# EEZ_CF-DIC_r5B5.net
KiCad netlist of a schematic drawn in EAGLE
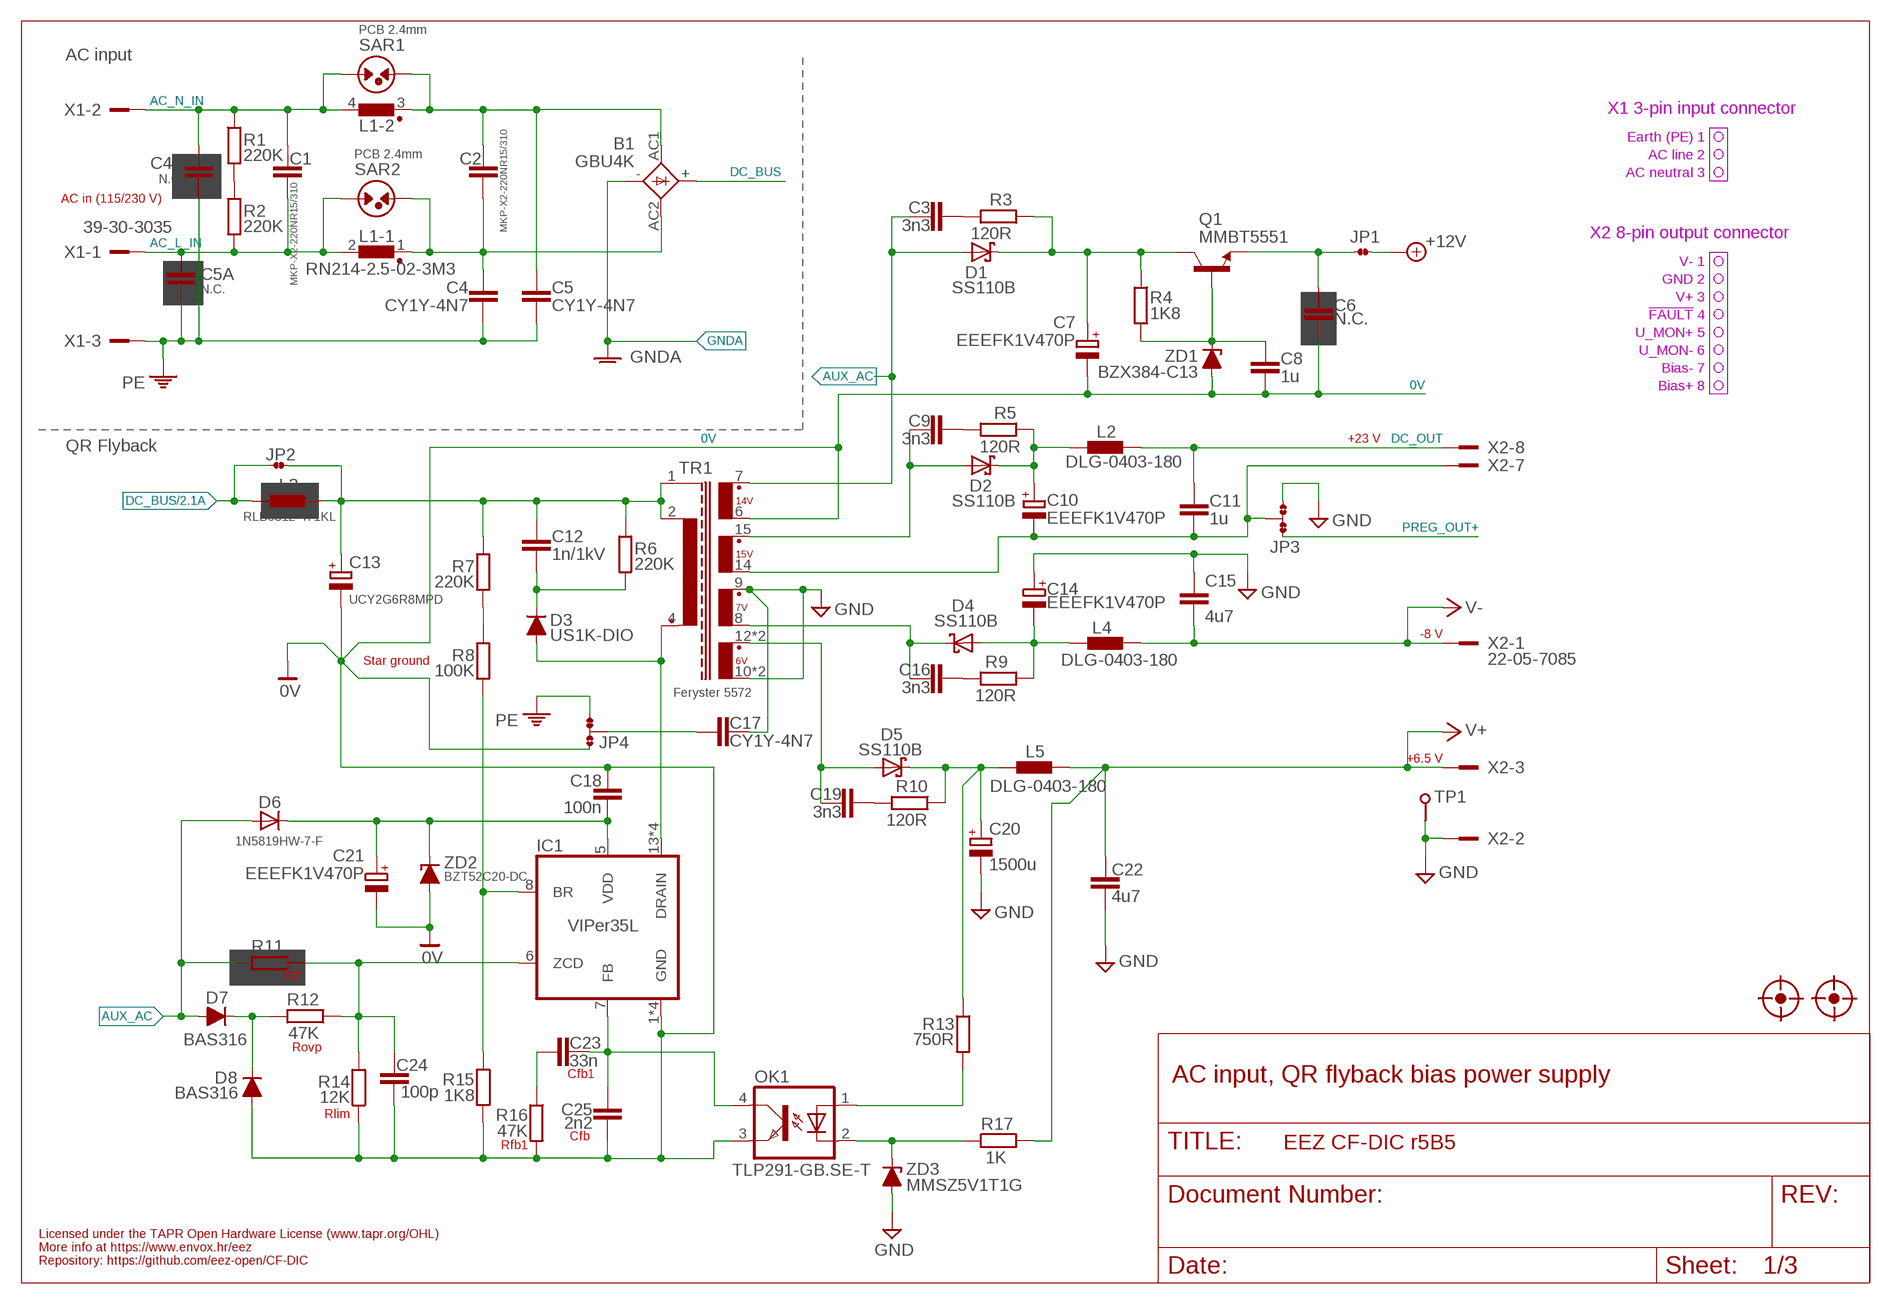
[diagram p0: schematic, sheet 1]
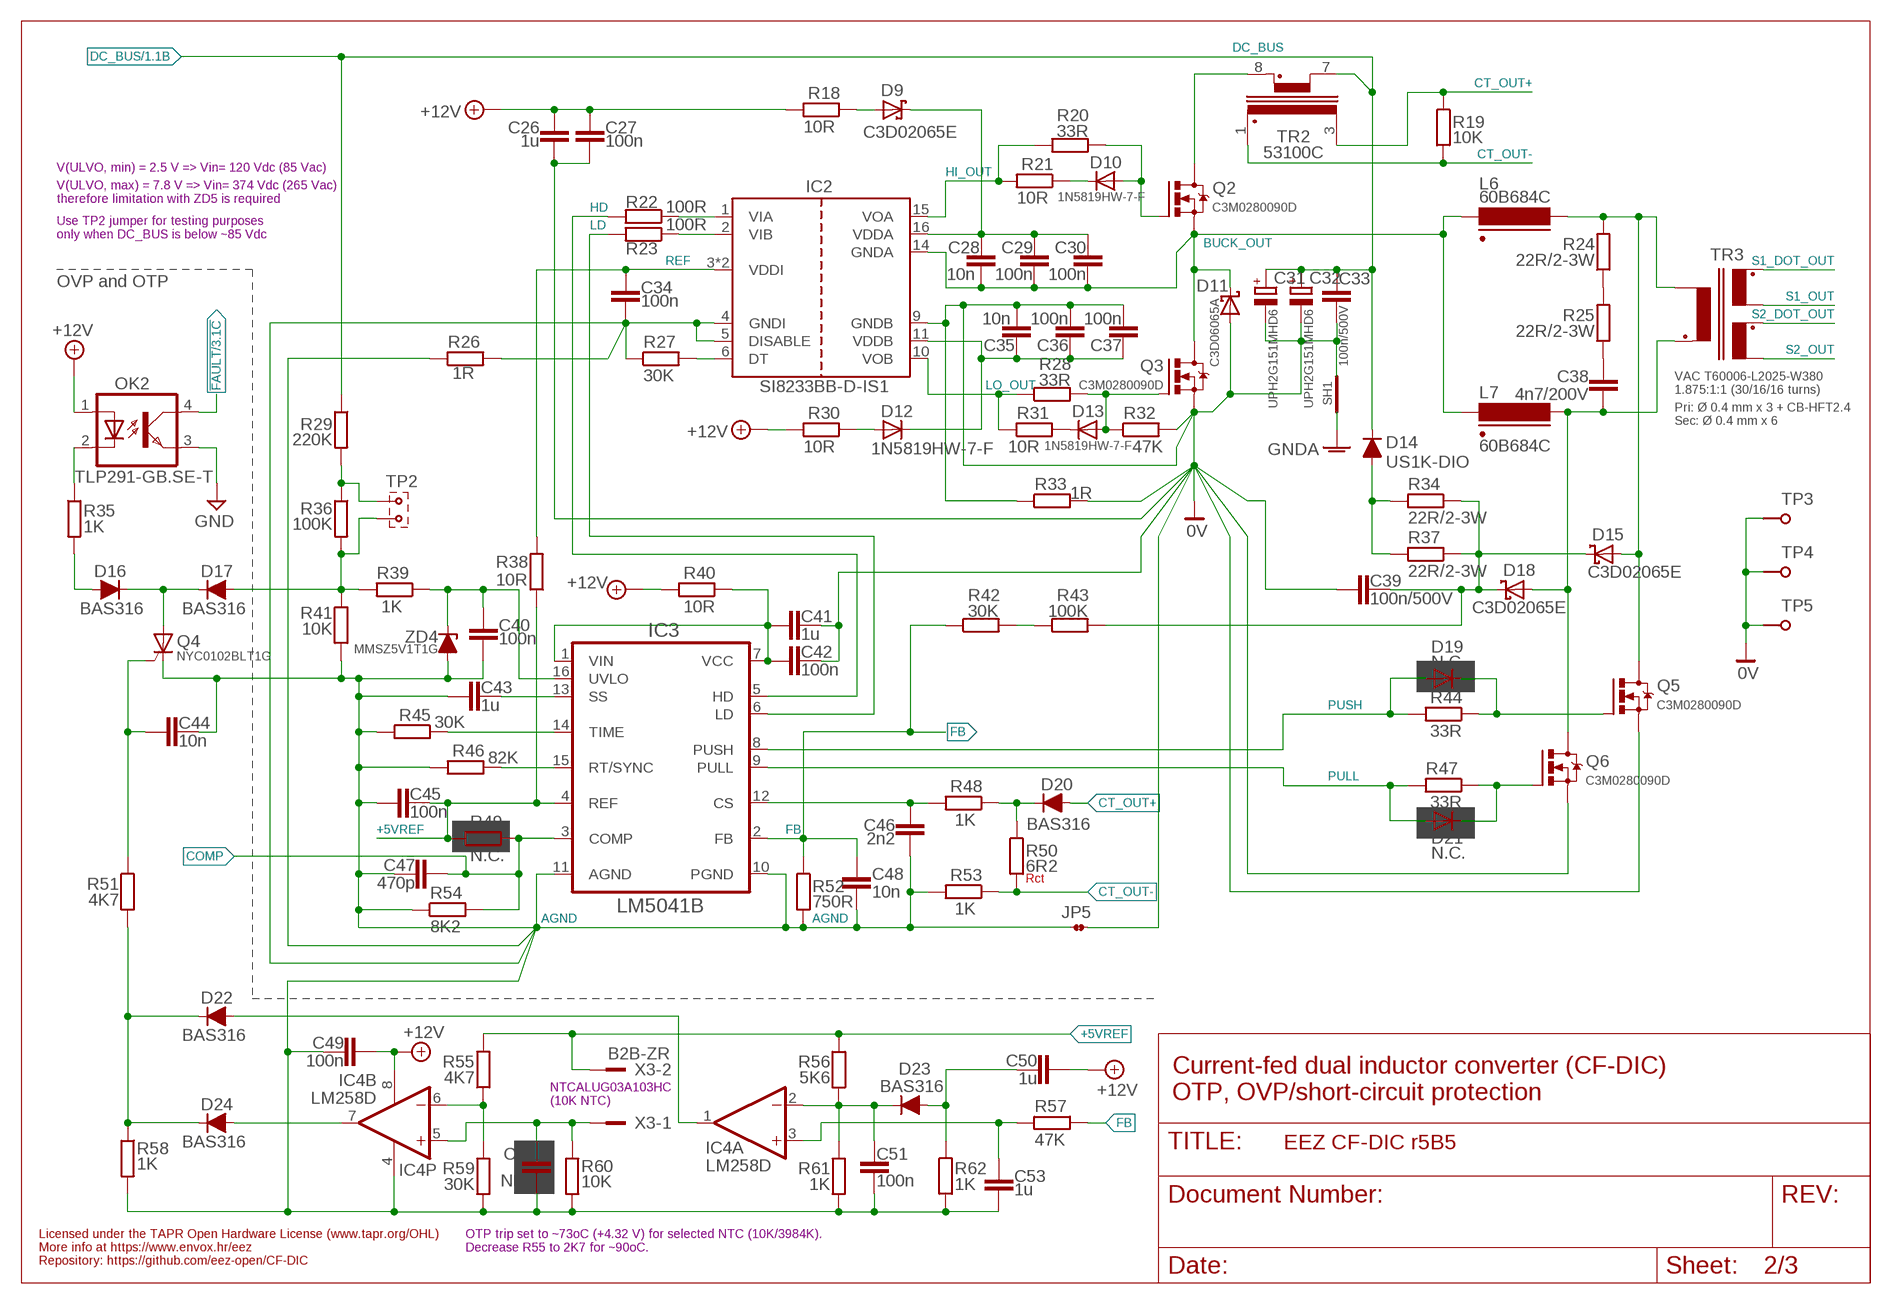
[diagram p1: schematic, sheet 2]
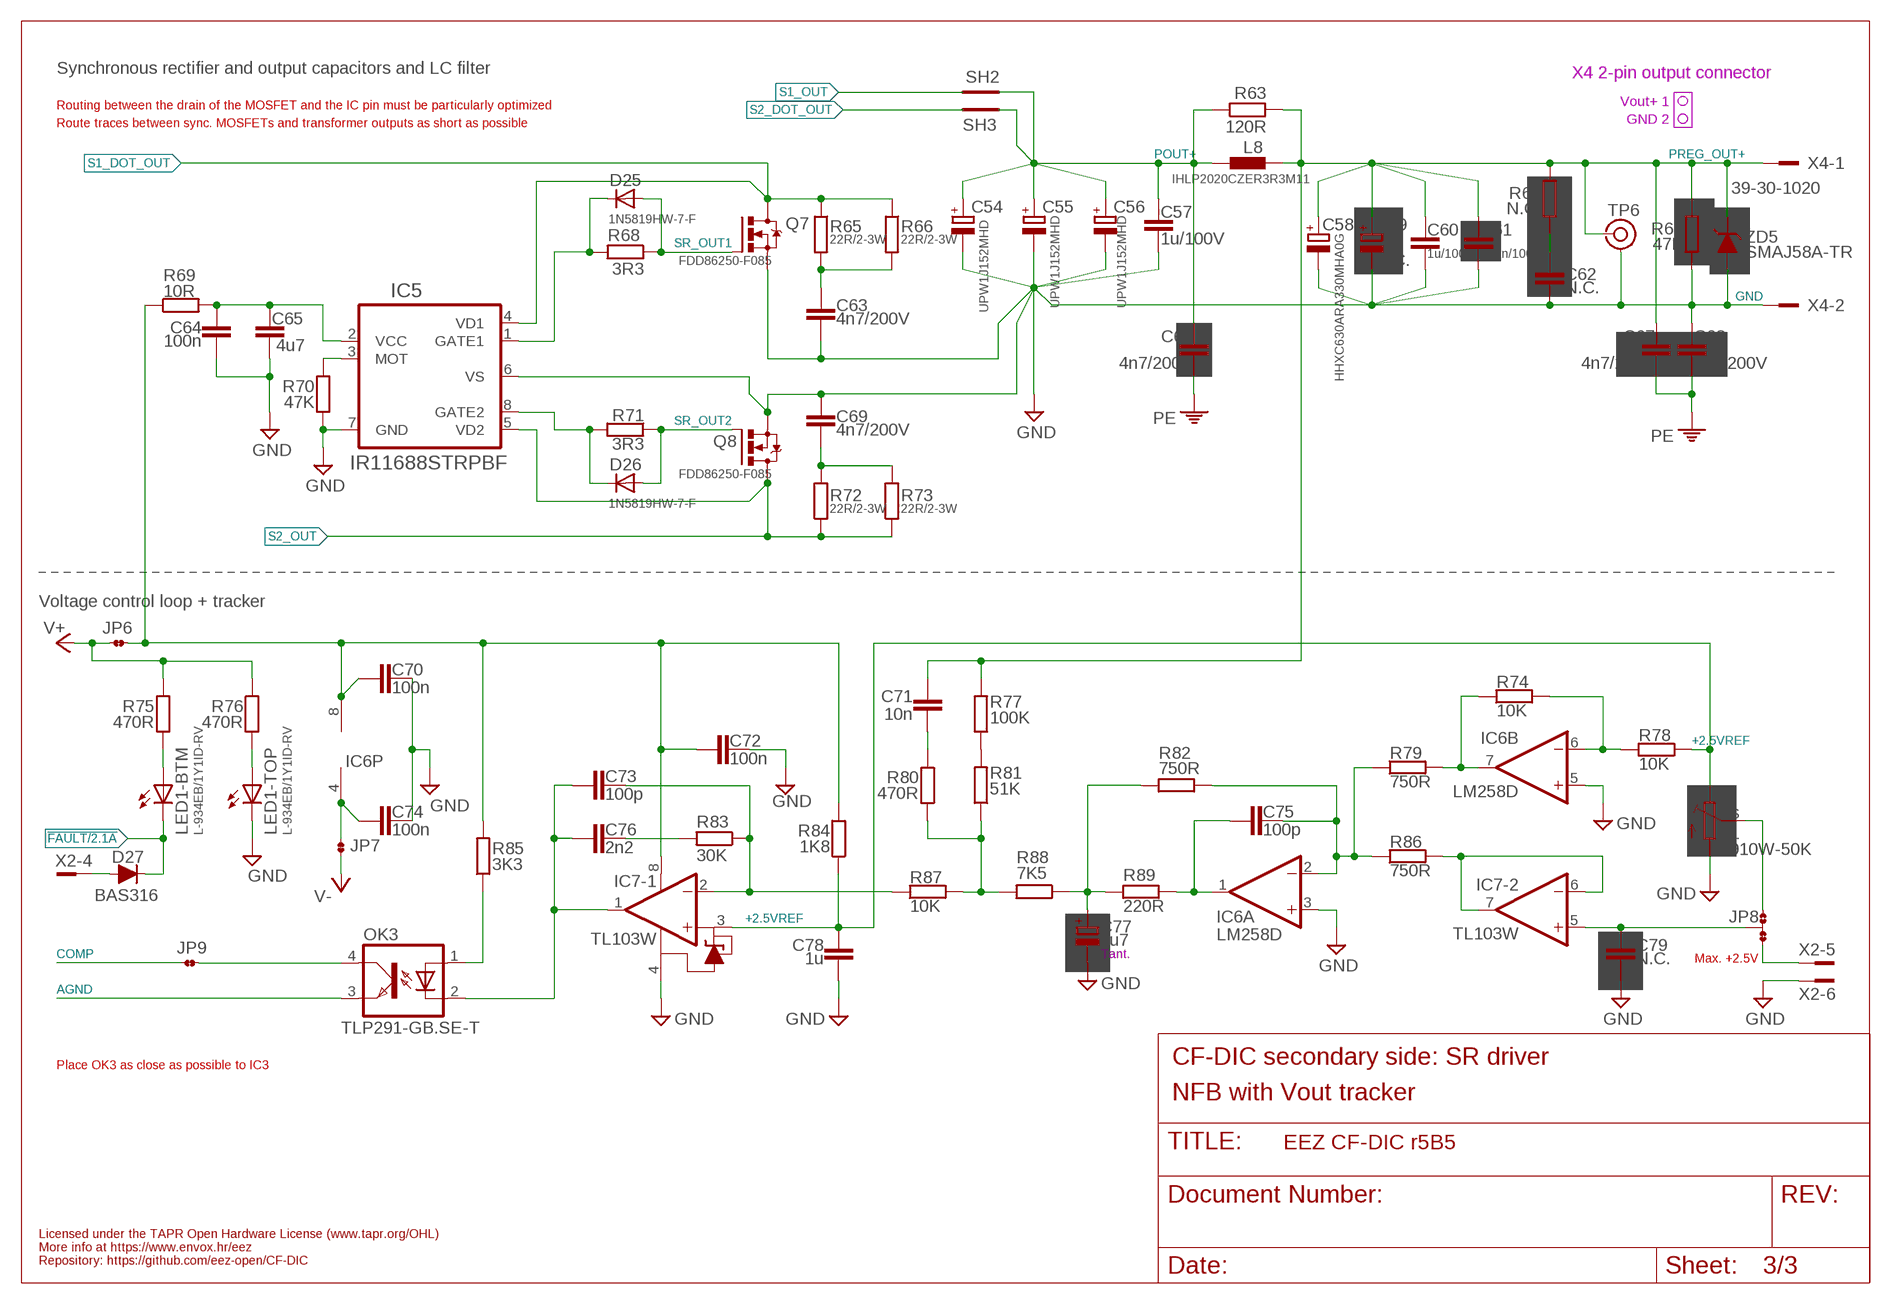
[diagram p2: schematic, sheet 3]

(export (version "E")
  (design (tool "Eeschema 10.0.6"))
  (components
    (comp (ref "B1")
      (value "GBU4K")
      (footprint "eagle-import:GBU4K_CRE")
      (libsource (lib "eagle-import") (part "BRIDGE-CREEPAGE"))
    )
    (comp (ref "C1")
      (value "MKP-X2-220NR15/310")
      (footprint "eagle-import:C150-072X183")
      (libsource (lib "eagle-import") (part "C-EU150-072X183"))
    )
    (comp (ref "C2")
      (value "MKP-X2-220NR15/310")
      (footprint "eagle-import:C150-072X183")
      (libsource (lib "eagle-import") (part "C-EU150-072X183"))
    )
    (comp (ref "C3")
      (value "3n3")
      (footprint "eagle-import:C0805")
      (libsource (lib "eagle-import") (part "C-EUC0805"))
    )
    (comp (ref "C4")
      (value "CY1Y-4N7")
      (footprint "eagle-import:CY075-032X103")
      (libsource (lib "eagle-import") (part "C-EUCY"))
    )
    (comp (ref "C4A")
      (value "N.C.")
      (footprint "eagle-import:CY075-032X103-ROTATED")
      (libsource (lib "eagle-import") (part "C-EUCY-ROTATED"))
    )
    (comp (ref "C5")
      (value "CY1Y-4N7")
      (footprint "eagle-import:CY075-032X103")
      (libsource (lib "eagle-import") (part "C-EUCY"))
    )
    (comp (ref "C5A")
      (value "N.C.")
      (footprint "eagle-import:CY075-032X103")
      (libsource (lib "eagle-import") (part "C-EUCY"))
    )
    (comp (ref "C6")
      (value "N.C.")
      (footprint "eagle-import:C0603")
      (libsource (lib "eagle-import") (part "C-EUC0603"))
    )
    (comp (ref "C7")
      (value "EEEFK1V470P")
      (footprint "eagle-import:CAPAE660X610N")
      (libsource (lib "eagle-import") (part "ECAPPANASONIC_H"))
    )
    (comp (ref "C8")
      (value "1u")
      (footprint "eagle-import:C0805")
      (libsource (lib "eagle-import") (part "C-EUC0805"))
    )
    (comp (ref "C9")
      (value "3n3")
      (footprint "eagle-import:C0805")
      (libsource (lib "eagle-import") (part "C-EUC0805"))
    )
    (comp (ref "C10")
      (value "EEEFK1V470P")
      (footprint "eagle-import:CAPAE660X610N")
      (libsource (lib "eagle-import") (part "ECAPPANASONIC_H"))
    )
    (comp (ref "C11")
      (value "1u")
      (footprint "eagle-import:C0805")
      (libsource (lib "eagle-import") (part "C-EUC0805"))
    )
    (comp (ref "C12")
      (value "1n/1kV")
      (footprint "eagle-import:C1210")
      (libsource (lib "eagle-import") (part "C-EUC1210"))
    )
    (comp (ref "C13")
      (value "UCY2G6R8MPD")
      (footprint "eagle-import:ECAP5_10.5")
      (libsource (lib "eagle-import") (part "ECAP5G_10.5MM"))
    )
    (comp (ref "C14")
      (value "EEEFK1V470P")
      (footprint "eagle-import:CAPAE660X610N")
      (libsource (lib "eagle-import") (part "ECAPPANASONIC_H"))
    )
    (comp (ref "C15")
      (value "4u7")
      (footprint "eagle-import:C1206")
      (libsource (lib "eagle-import") (part "C-EUC1206"))
    )
    (comp (ref "C16")
      (value "3n3")
      (footprint "eagle-import:C0805")
      (libsource (lib "eagle-import") (part "C-EUC0805"))
    )
    (comp (ref "C17")
      (value "CY1Y-4N7")
      (footprint "eagle-import:CY075-032X103")
      (libsource (lib "eagle-import") (part "C-EUCY"))
    )
    (comp (ref "C18")
      (value "100n")
      (footprint "eagle-import:C0603")
      (libsource (lib "eagle-import") (part "C-EUC0603"))
    )
    (comp (ref "C19")
      (value "3n3")
      (footprint "eagle-import:C0805")
      (libsource (lib "eagle-import") (part "C-EUC0805"))
    )
    (comp (ref "C20")
      (value "1500u")
      (footprint "eagle-import:ECAP5_13")
      (libsource (lib "eagle-import") (part "ECAP5G_13MM"))
    )
    (comp (ref "C21")
      (value "EEEFK1V470P")
      (footprint "eagle-import:CAPAE660X610N")
      (libsource (lib "eagle-import") (part "ECAPPANASONIC_H"))
    )
    (comp (ref "C22")
      (value "4u7")
      (footprint "eagle-import:C1206")
      (libsource (lib "eagle-import") (part "C-EUC1206"))
    )
    (comp (ref "C23")
      (value "33n")
      (footprint "eagle-import:C0805")
      (libsource (lib "eagle-import") (part "C-EUC0805"))
    )
    (comp (ref "C24")
      (value "100p")
      (footprint "eagle-import:C0805")
      (libsource (lib "eagle-import") (part "C-EUC0805"))
    )
    (comp (ref "C25")
      (value "2n2")
      (footprint "eagle-import:C0805")
      (libsource (lib "eagle-import") (part "C-EUC0805"))
    )
    (comp (ref "D1")
      (value "SS110B")
      (footprint "eagle-import:SMB")
      (libsource (lib "eagle-import") (part "SCHOTTKYSMB"))
    )
    (comp (ref "D2")
      (value "SS110B")
      (footprint "eagle-import:SMB")
      (libsource (lib "eagle-import") (part "SCHOTTKYSMB"))
    )
    (comp (ref "D3")
      (value "US1K-DIO")
      (footprint "eagle-import:DO214AA")
      (libsource (lib "eagle-import") (part "DIODEDO214AA"))
    )
    (comp (ref "D4")
      (value "SS110B")
      (footprint "eagle-import:SMB")
      (libsource (lib "eagle-import") (part "SCHOTTKYSMB"))
    )
    (comp (ref "D5")
      (value "SS110B")
      (footprint "eagle-import:SMB")
      (libsource (lib "eagle-import") (part "SCHOTTKYSMB"))
    )
    (comp (ref "D6")
      (value "1N5819HW-7-F")
      (footprint "eagle-import:SOD323-W")
      (libsource (lib "eagle-import") (part "DIODE-SOD323-W"))
    )
    (comp (ref "D7")
      (value "BAS316")
      (footprint "eagle-import:SOD323-R")
      (libsource (lib "eagle-import") (part "DIODESOD323R"))
    )
    (comp (ref "D8")
      (value "BAS316")
      (footprint "eagle-import:SOD323-R")
      (libsource (lib "eagle-import") (part "DIODESOD323R"))
    )
    (comp (ref "FM1")
      (value "FIDUCIAL_2")
      (footprint "eagle-import:FIDUCIAL_DUAL")
      (libsource (lib "eagle-import") (part "FIDUCIAL_2"))
    )
    (comp (ref "FM2")
      (value "FIDUCIAL_2")
      (footprint "eagle-import:FIDUCIAL_DUAL")
      (libsource (lib "eagle-import") (part "FIDUCIAL_2"))
    )
    (comp (ref "IC1")
      (value "VIPer35L")
      (footprint "eagle-import:SOIC-16")
      (libsource (lib "eagle-import") (part "VIPER35"))
    )
    (comp (ref "JP1")
      (value "JP2-NOCUT")
      (footprint "eagle-import:JP2-NOCUT")
      (libsource (lib "eagle-import") (part "JP2-NOCUT"))
    )
    (comp (ref "JP2")
      (value "JP2-NOCUT")
      (footprint "eagle-import:JP2-NOCUT")
      (libsource (lib "eagle-import") (part "JP2-NOCUT"))
    )
    (comp (ref "JP3")
      (value "JP3-CUT")
      (footprint "eagle-import:JP3-CUT")
      (libsource (lib "eagle-import") (part "JP3-CUT"))
    )
    (comp (ref "JP4")
      (value "JP3-CUT")
      (footprint "eagle-import:JP3-CUT")
      (libsource (lib "eagle-import") (part "JP3-CUT"))
    )
    (comp (ref "L1")
      (value "RN214-2.5-02-3M3")
      (footprint "eagle-import:RN214")
      (fields (field (name "FARNELL") "1191518"))
      (libsource (lib "eagle-import") (part "EEZ_inductors_and_transformers_RN214"))
    )
    (comp (ref "L2")
      (value "DLG-0403-180")
      (footprint "eagle-import:DE0403")
      (libsource (lib "eagle-import") (part "EEZ_inductors_and_transformers_DE0403"))
    )
    (comp (ref "L3")
      (value "RLB0812-471KL")
      (footprint "eagle-import:FERSYTER_DSZ6")
      (libsource (lib "eagle-import") (part "FERYSTER_DSZ6"))
    )
    (comp (ref "L4")
      (value "DLG-0403-180")
      (footprint "eagle-import:DE0403")
      (libsource (lib "eagle-import") (part "EEZ_inductors_and_transformers_DE0403"))
    )
    (comp (ref "L5")
      (value "DLG-0403-180")
      (footprint "eagle-import:DE0403")
      (libsource (lib "eagle-import") (part "EEZ_inductors_and_transformers_DE0403"))
    )
    (comp (ref "OK1")
      (value "TLP291-GB.SE-T")
      (footprint "eagle-import:SO4")
      (libsource (lib "eagle-import") (part "TLP291"))
    )
    (comp (ref "Q1")
      (value "MMBT5551")
      (footprint "eagle-import:SOT23-BEC")
      (libsource (lib "eagle-import") (part "-NPN-SOT23-BECMMBT5551LT1"))
    )
    (comp (ref "R1")
      (value "220K")
      (footprint "eagle-import:R1206")
      (libsource (lib "eagle-import") (part "R-EU_R1206"))
    )
    (comp (ref "R2")
      (value "220K")
      (footprint "eagle-import:R1206")
      (libsource (lib "eagle-import") (part "R-EU_R1206"))
    )
    (comp (ref "R3")
      (value "120R")
      (footprint "eagle-import:R0805")
      (libsource (lib "eagle-import") (part "R-EU_R0805"))
    )
    (comp (ref "R4")
      (value "1K8")
      (footprint "eagle-import:R0805")
      (libsource (lib "eagle-import") (part "R-EU_R0805"))
    )
    (comp (ref "R5")
      (value "120R")
      (footprint "eagle-import:R0805")
      (libsource (lib "eagle-import") (part "R-EU_R0805"))
    )
    (comp (ref "R6")
      (value "220K")
      (footprint "eagle-import:R1206")
      (libsource (lib "eagle-import") (part "R-EU_R1206"))
    )
    (comp (ref "R7")
      (value "220K")
      (footprint "eagle-import:R1206")
      (libsource (lib "eagle-import") (part "R-EU_R1206"))
    )
    (comp (ref "R8")
      (value "100K")
      (footprint "eagle-import:R0805")
      (libsource (lib "eagle-import") (part "R-EU_R0805"))
    )
    (comp (ref "R9")
      (value "120R")
      (footprint "eagle-import:R0805")
      (libsource (lib "eagle-import") (part "R-EU_R0805"))
    )
    (comp (ref "R10")
      (value "120R")
      (footprint "eagle-import:R0805")
      (libsource (lib "eagle-import") (part "R-EU_R0805"))
    )
    (comp (ref "R11")
      (value "N.C.")
      (footprint "eagle-import:R0805")
      (libsource (lib "eagle-import") (part "R-EU_R0805"))
    )
    (comp (ref "R12")
      (value "47K")
      (footprint "eagle-import:R0805")
      (libsource (lib "eagle-import") (part "R-EU_R0805"))
    )
    (comp (ref "R13")
      (value "750R")
      (footprint "eagle-import:R0805")
      (libsource (lib "eagle-import") (part "R-EU_R0805"))
    )
    (comp (ref "R14")
      (value "12K")
      (footprint "eagle-import:R0805")
      (libsource (lib "eagle-import") (part "R-EU_R0805"))
    )
    (comp (ref "R15")
      (value "1K8")
      (footprint "eagle-import:R0805")
      (libsource (lib "eagle-import") (part "R-EU_R0805"))
    )
    (comp (ref "R16")
      (value "47K")
      (footprint "eagle-import:R0805")
      (libsource (lib "eagle-import") (part "R-EU_R0805"))
    )
    (comp (ref "R17")
      (value "1K")
      (footprint "eagle-import:R0805")
      (libsource (lib "eagle-import") (part "R-EU_R0805"))
    )
    (comp (ref "SAR1")
      (value "PCB 2.4mm")
      (footprint "eagle-import:PCB-SAR_2.4MM")
      (libsource (lib "eagle-import") (part "SARPCB-2.4MM"))
    )
    (comp (ref "SAR2")
      (value "PCB 2.4mm")
      (footprint "eagle-import:PCB-SAR_2.4MM")
      (libsource (lib "eagle-import") (part "SARPCB-2.4MM"))
    )
    (comp (ref "TP1")
      (value "PCB_TEST_TABSHIELD")
      (footprint "eagle-import:PCB_SHIELD_TAB")
      (libsource (lib "eagle-import") (part "PCB_TEST_TABSHIELD"))
    )
    (comp (ref "TR1")
      (value "Feryster 5572")
      (footprint "eagle-import:FERYSTER_5572")
      (libsource (lib "eagle-import") (part "EEZ_inductors_and_transformers_FERYSTER_5572"))
    )
    (comp (ref "X1")
      (value "39-30-3035")
      (footprint "eagle-import:MINIFIT_6659-3_CRE")
      (libsource (lib "eagle-import") (part "MINIFIT_6659-3-CRE"))
    )
    (comp (ref "X2")
      (value "22-05-7085")
      (footprint "eagle-import:SPOX_22-05-7085")
      (libsource (lib "eagle-import") (part "SPOX_22-05-7085"))
    )
    (comp (ref "ZD1")
      (value "BZX384-C13")
      (footprint "eagle-import:SOD323-W")
      (libsource (lib "eagle-import") (part "ZENER-DIODESOD323"))
    )
    (comp (ref "ZD2")
      (value "BZT52C20-DC")
      (footprint "eagle-import:SOD123")
      (libsource (lib "eagle-import") (part "ZENER-DIODESOD123"))
    )
    (comp (ref "ZD3")
      (value "MMSZ5V1T1G")
      (footprint "eagle-import:SOD323-W")
      (libsource (lib "eagle-import") (part "ZENER-DIODESOD323"))
    )
    (comp (ref "C54")
      (value "UPW1J152MHD")
      (footprint "eagle-import:ECAP7.5_18")
      (libsource (lib "eagle-import") (part "ECAP7.5G_18MM"))
    )
    (comp (ref "C55")
      (value "UPW1J152MHD")
      (footprint "eagle-import:ECAP7.5_18")
      (libsource (lib "eagle-import") (part "ECAP7.5G_18MM"))
    )
    (comp (ref "C56")
      (value "UPW1J152MHD")
      (footprint "eagle-import:ECAP7.5_18")
      (libsource (lib "eagle-import") (part "ECAP7.5G_18MM"))
    )
    (comp (ref "C57")
      (value "1u/100V")
      (footprint "eagle-import:C1206")
      (libsource (lib "eagle-import") (part "C-EUC1206"))
    )
    (comp (ref "C58")
      (value "HHXC630ARA330MHA0G")
      (footprint "eagle-import:CAPAE830X1050N")
      (libsource (lib "eagle-import") (part "ECAPSMD8.3MM/HA0"))
    )
    (comp (ref "C59")
      (value "N.C.")
      (footprint "eagle-import:CAPAE830X1050N")
      (libsource (lib "eagle-import") (part "ECAPSMD8.3MM/HA0"))
    )
    (comp (ref "C60")
      (value "1u/100V")
      (footprint "eagle-import:C1206")
      (libsource (lib "eagle-import") (part "C-EUC1206"))
    )
    (comp (ref "C61")
      (value "100n/100V")
      (footprint "eagle-import:C1206")
      (libsource (lib "eagle-import") (part "C-EUC1206"))
    )
    (comp (ref "C62")
      (value "N.C.")
      (footprint "eagle-import:C1206")
      (libsource (lib "eagle-import") (part "C-EUC1206"))
    )
    (comp (ref "C63")
      (value "4n7/200V")
      (footprint "eagle-import:C1206")
      (libsource (lib "eagle-import") (part "C-EUC1206"))
    )
    (comp (ref "C64")
      (value "100n")
      (footprint "eagle-import:C0603")
      (libsource (lib "eagle-import") (part "C-EUC0603"))
    )
    (comp (ref "C65")
      (value "4u7")
      (footprint "eagle-import:C1206")
      (libsource (lib "eagle-import") (part "C-EUC1206"))
    )
    (comp (ref "C66")
      (value "4n7/200V")
      (footprint "eagle-import:C1206")
      (libsource (lib "eagle-import") (part "C-EUC1206"))
    )
    (comp (ref "C67")
      (value "4n7/200V")
      (footprint "eagle-import:C1206")
      (libsource (lib "eagle-import") (part "C-EUC1206"))
    )
    (comp (ref "C68")
      (value "4n7/200V")
      (footprint "eagle-import:C1206")
      (libsource (lib "eagle-import") (part "C-EUC1206"))
    )
    (comp (ref "C69")
      (value "4n7/200V")
      (footprint "eagle-import:C1206")
      (libsource (lib "eagle-import") (part "C-EUC1206"))
    )
    (comp (ref "C70")
      (value "100n")
      (footprint "eagle-import:C0603")
      (libsource (lib "eagle-import") (part "C-EUC0603"))
    )
    (comp (ref "C71")
      (value "10n")
      (footprint "eagle-import:C0603")
      (libsource (lib "eagle-import") (part "C-EUC0603"))
    )
    (comp (ref "C72")
      (value "100n")
      (footprint "eagle-import:C0603")
      (libsource (lib "eagle-import") (part "C-EUC0603"))
    )
    (comp (ref "C73")
      (value "100p")
      (footprint "eagle-import:C0805")
      (libsource (lib "eagle-import") (part "C-EUC0805"))
    )
    (comp (ref "C74")
      (value "100n")
      (footprint "eagle-import:C0603")
      (libsource (lib "eagle-import") (part "C-EUC0603"))
    )
    (comp (ref "C75")
      (value "100p")
      (footprint "eagle-import:C0805")
      (libsource (lib "eagle-import") (part "C-EUC0805"))
    )
    (comp (ref "C76")
      (value "2n2")
      (footprint "eagle-import:C0805")
      (libsource (lib "eagle-import") (part "C-EUC0805"))
    )
    (comp (ref "C77")
      (value "4u7")
      (footprint "eagle-import:EC1206")
      (libsource (lib "eagle-import") (part "ECAP1206"))
    )
    (comp (ref "C78")
      (value "1u")
      (footprint "eagle-import:C0805")
      (libsource (lib "eagle-import") (part "C-EUC0805"))
    )
    (comp (ref "C79")
      (value "N.C.")
      (footprint "eagle-import:C0805")
      (libsource (lib "eagle-import") (part "C-EUC0805"))
    )
    (comp (ref "D25")
      (value "1N5819HW-7-F")
      (footprint "eagle-import:SOD323-W")
      (libsource (lib "eagle-import") (part "DIODE-SOD323-W"))
    )
    (comp (ref "D26")
      (value "1N5819HW-7-F")
      (footprint "eagle-import:SOD323-W")
      (libsource (lib "eagle-import") (part "DIODE-SOD323-W"))
    )
    (comp (ref "D27")
      (value "BAS316")
      (footprint "eagle-import:SOD323-R")
      (libsource (lib "eagle-import") (part "DIODESOD323R"))
    )
    (comp (ref "IC5")
      (value "IR11688STRPBF")
      (footprint "eagle-import:SO8")
      (libsource (lib "eagle-import") (part "IR11688"))
    )
    (comp (ref "IC6")
      (value "LM258D")
      (footprint "eagle-import:SOIC127P600X173-8N")
      (libsource (lib "eagle-import") (part "TL072SOIC8"))
    )
    (comp (ref "IC7")
      (value "TL103W")
      (footprint "eagle-import:SOIC127P600X173-8N")
      (libsource (lib "eagle-import") (part "TL103W"))
    )
    (comp (ref "JP6")
      (value "JP2-NOCUT")
      (footprint "eagle-import:JP2-NOCUT")
      (libsource (lib "eagle-import") (part "JP2-NOCUT"))
    )
    (comp (ref "JP7")
      (value "JP2-NOCUT")
      (footprint "eagle-import:JP2-NOCUT")
      (libsource (lib "eagle-import") (part "JP2-NOCUT"))
    )
    (comp (ref "JP8")
      (value "JP3-CUT")
      (footprint "eagle-import:JP3-CUT")
      (libsource (lib "eagle-import") (part "JP3-CUT"))
    )
    (comp (ref "JP9")
      (value "JP2-NOCUT")
      (footprint "eagle-import:JP2-NOCUT")
      (libsource (lib "eagle-import") (part "JP2-NOCUT"))
    )
    (comp (ref "L8")
      (value "IHLP2020CZER3R3M11")
      (footprint "eagle-import:IHLP-2020BZ-11")
      (libsource (lib "eagle-import") (part "EEZ_inductors_and_transformers_IHLP-2020BZ-11"))
    )
    (comp (ref "LED1")
      (value "L-934EB/1Y1ID-RV")
      (footprint "eagle-import:L-934EB")
      (libsource (lib "eagle-import") (part "LED_L-934EB/1Y1ID-RV"))
    )
    (comp (ref "OK3")
      (value "TLP291-GB.SE-T")
      (footprint "eagle-import:SO4")
      (libsource (lib "eagle-import") (part "TLP291"))
    )
    (comp (ref "P1")
      (value "T910W-50K")
      (footprint "eagle-import:S64W")
      (libsource (lib "eagle-import") (part "TPOT-S64W"))
    )
    (comp (ref "Q7")
      (value "FDD86250-F085")
      (footprint "eagle-import:TO263")
      (libsource (lib "eagle-import") (part "N-MOSFETTO263"))
    )
    (comp (ref "Q8")
      (value "FDD86250-F085")
      (footprint "eagle-import:TO263")
      (libsource (lib "eagle-import") (part "N-MOSFETTO263"))
    )
    (comp (ref "R63")
      (value "120R")
      (footprint "eagle-import:R0805")
      (libsource (lib "eagle-import") (part "R-EU_R0805"))
    )
    (comp (ref "R64")
      (value "N.C.")
      (footprint "eagle-import:R1210")
      (libsource (lib "eagle-import") (part "R-EU_R1210"))
    )
    (comp (ref "R65")
      (value "22R/2-3W")
      (footprint "eagle-import:R2512")
      (libsource (lib "eagle-import") (part "R-EU_R2512"))
    )
    (comp (ref "R66")
      (value "22R/2-3W")
      (footprint "eagle-import:R2512")
      (libsource (lib "eagle-import") (part "R-EU_R2512"))
    )
    (comp (ref "R67")
      (value "47K")
      (footprint "eagle-import:R0805")
      (libsource (lib "eagle-import") (part "R-EU_R0805"))
    )
    (comp (ref "R68")
      (value "3R3")
      (footprint "eagle-import:R0805")
      (libsource (lib "eagle-import") (part "R-EU_R0805"))
    )
    (comp (ref "R69")
      (value "10R")
      (footprint "eagle-import:R0805")
      (libsource (lib "eagle-import") (part "R-EU_R0805"))
    )
    (comp (ref "R70")
      (value "47K")
      (footprint "eagle-import:R0805")
      (libsource (lib "eagle-import") (part "R-EU_R0805"))
    )
    (comp (ref "R71")
      (value "3R3")
      (footprint "eagle-import:R0805")
      (libsource (lib "eagle-import") (part "R-EU_R0805"))
    )
    (comp (ref "R72")
      (value "22R/2-3W")
      (footprint "eagle-import:R2512")
      (libsource (lib "eagle-import") (part "R-EU_R2512"))
    )
    (comp (ref "R73")
      (value "22R/2-3W")
      (footprint "eagle-import:R2512")
      (libsource (lib "eagle-import") (part "R-EU_R2512"))
    )
    (comp (ref "R74")
      (value "10K")
      (footprint "eagle-import:R0805")
      (libsource (lib "eagle-import") (part "R-EU_R0805"))
    )
    (comp (ref "R75")
      (value "470R")
      (footprint "eagle-import:R0805")
      (libsource (lib "eagle-import") (part "R-EU_R0805"))
    )
    (comp (ref "R76")
      (value "470R")
      (footprint "eagle-import:R0805")
      (libsource (lib "eagle-import") (part "R-EU_R0805"))
    )
    (comp (ref "R77")
      (value "100K")
      (footprint "eagle-import:R0805")
      (libsource (lib "eagle-import") (part "R-EU_R0805"))
    )
    (comp (ref "R78")
      (value "10K")
      (footprint "eagle-import:R0805")
      (libsource (lib "eagle-import") (part "R-EU_R0805"))
    )
    (comp (ref "R79")
      (value "750R")
      (footprint "eagle-import:R0805")
      (libsource (lib "eagle-import") (part "R-EU_R0805"))
    )
    (comp (ref "R80")
      (value "470R")
      (footprint "eagle-import:R0805")
      (libsource (lib "eagle-import") (part "R-EU_R0805"))
    )
    (comp (ref "R81")
      (value "51K")
      (footprint "eagle-import:R0805")
      (libsource (lib "eagle-import") (part "R-EU_R0805"))
    )
    (comp (ref "R82")
      (value "750R")
      (footprint "eagle-import:R0805")
      (libsource (lib "eagle-import") (part "R-EU_R0805"))
    )
    (comp (ref "R83")
      (value "30K")
      (footprint "eagle-import:R0805")
      (libsource (lib "eagle-import") (part "R-EU_R0805"))
    )
    (comp (ref "R84")
      (value "1K8")
      (footprint "eagle-import:R0805")
      (libsource (lib "eagle-import") (part "R-EU_R0805"))
    )
    (comp (ref "R85")
      (value "3K3")
      (footprint "eagle-import:R0805")
      (libsource (lib "eagle-import") (part "R-EU_R0805"))
    )
    (comp (ref "R86")
      (value "750R")
      (footprint "eagle-import:R0805")
      (libsource (lib "eagle-import") (part "R-EU_R0805"))
    )
    (comp (ref "R87")
      (value "10K")
      (footprint "eagle-import:R0805")
      (libsource (lib "eagle-import") (part "R-EU_R0805"))
    )
    (comp (ref "R88")
      (value "7K5")
      (footprint "eagle-import:R0805")
      (libsource (lib "eagle-import") (part "R-EU_R0805"))
    )
    (comp (ref "R89")
      (value "220R")
      (footprint "eagle-import:R0805")
      (libsource (lib "eagle-import") (part "R-EU_R0805"))
    )
    (comp (ref "SH2")
      (value "SHORTNOHOLE")
      (footprint "eagle-import:SHORT_NOHOLE")
      (libsource (lib "eagle-import") (part "SHORTNOHOLE"))
    )
    (comp (ref "SH3")
      (value "SHORTNOHOLE")
      (footprint "eagle-import:SHORT_NOHOLE")
      (libsource (lib "eagle-import") (part "SHORTNOHOLE"))
    )
    (comp (ref "TP6")
      (value "TEST_POINT-2")
      (footprint "eagle-import:TP_1.1MM_2")
      (libsource (lib "eagle-import") (part "TEST_POINT-2"))
    )
    (comp (ref "X4")
      (value "39-30-1020")
      (footprint "eagle-import:MINIFIT_39301020")
      (libsource (lib "eagle-import") (part "MINIFIT_39301020"))
    )
    (comp (ref "ZD5")
      (value "SMAJ58A-TR")
      (footprint "eagle-import:DO214AC")
      (libsource (lib "eagle-import") (part "PSMAXX"))
    )
    (comp (ref "C26")
      (value "1u")
      (footprint "eagle-import:C0805")
      (libsource (lib "eagle-import") (part "C-EUC0805"))
    )
    (comp (ref "C27")
      (value "100n")
      (footprint "eagle-import:C0603")
      (libsource (lib "eagle-import") (part "C-EUC0603"))
    )
    (comp (ref "C28")
      (value "10n")
      (footprint "eagle-import:C0603")
      (libsource (lib "eagle-import") (part "C-EUC0603"))
    )
    (comp (ref "C29")
      (value "100n")
      (footprint "eagle-import:C0603")
      (libsource (lib "eagle-import") (part "C-EUC0603"))
    )
    (comp (ref "C30")
      (value "100n")
      (footprint "eagle-import:C0603")
      (libsource (lib "eagle-import") (part "C-EUC0603"))
    )
    (comp (ref "C31")
      (value "UPH2G151MHD6")
      (footprint "eagle-import:ECAP7.5_18")
      (libsource (lib "eagle-import") (part "ECAP7.5G_18MM"))
    )
    (comp (ref "C32")
      (value "UPH2G151MHD6")
      (footprint "eagle-import:ECAP7.5_18")
      (libsource (lib "eagle-import") (part "ECAP7.5G_18MM"))
    )
    (comp (ref "C33")
      (value "100n/500V")
      (footprint "eagle-import:C1812")
      (libsource (lib "eagle-import") (part "C-EUC1812"))
    )
    (comp (ref "C34")
      (value "100n")
      (footprint "eagle-import:C0603")
      (libsource (lib "eagle-import") (part "C-EUC0603"))
    )
    (comp (ref "C35")
      (value "10n")
      (footprint "eagle-import:C0603")
      (libsource (lib "eagle-import") (part "C-EUC0603"))
    )
    (comp (ref "C36")
      (value "100n")
      (footprint "eagle-import:C0603")
      (libsource (lib "eagle-import") (part "C-EUC0603"))
    )
    (comp (ref "C37")
      (value "100n")
      (footprint "eagle-import:C0603")
      (libsource (lib "eagle-import") (part "C-EUC0603"))
    )
    (comp (ref "C38")
      (value "4n7/200V")
      (footprint "eagle-import:C1210")
      (libsource (lib "eagle-import") (part "C-EUC1210"))
    )
    (comp (ref "C39")
      (value "100n/500V")
      (footprint "eagle-import:C1812")
      (libsource (lib "eagle-import") (part "C-EUC1812"))
    )
    (comp (ref "C40")
      (value "100n")
      (footprint "eagle-import:C0603")
      (libsource (lib "eagle-import") (part "C-EUC0603"))
    )
    (comp (ref "C41")
      (value "1u")
      (footprint "eagle-import:C0805")
      (libsource (lib "eagle-import") (part "C-EUC0805"))
    )
    (comp (ref "C42")
      (value "100n")
      (footprint "eagle-import:C0603")
      (libsource (lib "eagle-import") (part "C-EUC0603"))
    )
    (comp (ref "C43")
      (value "1u")
      (footprint "eagle-import:C0805")
      (libsource (lib "eagle-import") (part "C-EUC0805"))
    )
    (comp (ref "C44")
      (value "10n")
      (footprint "eagle-import:C0603")
      (libsource (lib "eagle-import") (part "C-EUC0603"))
    )
    (comp (ref "C45")
      (value "100n")
      (footprint "eagle-import:C0603")
      (libsource (lib "eagle-import") (part "C-EUC0603"))
    )
    (comp (ref "C46")
      (value "2n2")
      (footprint "eagle-import:C0805")
      (libsource (lib "eagle-import") (part "C-EUC0805"))
    )
    (comp (ref "C47")
      (value "470p")
      (footprint "eagle-import:C0805")
      (libsource (lib "eagle-import") (part "C-EUC0805"))
    )
    (comp (ref "C48")
      (value "10n")
      (footprint "eagle-import:C0603")
      (libsource (lib "eagle-import") (part "C-EUC0603"))
    )
    (comp (ref "C49")
      (value "100n")
      (footprint "eagle-import:C0603")
      (libsource (lib "eagle-import") (part "C-EUC0603"))
    )
    (comp (ref "C50")
      (value "1u")
      (footprint "eagle-import:C0805")
      (libsource (lib "eagle-import") (part "C-EUC0805"))
    )
    (comp (ref "C51")
      (value "100n")
      (footprint "eagle-import:C0603")
      (libsource (lib "eagle-import") (part "C-EUC0603"))
    )
    (comp (ref "C52")
      (value "N.C.")
      (footprint "eagle-import:C0603")
      (libsource (lib "eagle-import") (part "C-EUC0603"))
    )
    (comp (ref "C53")
      (value "1u")
      (footprint "eagle-import:C0805")
      (libsource (lib "eagle-import") (part "C-EUC0805"))
    )
    (comp (ref "D9")
      (value "C3D02065E")
      (footprint "eagle-import:TO252")
      (libsource (lib "eagle-import") (part "SCHOTTKY-SIC"))
    )
    (comp (ref "D10")
      (value "1N5819HW-7-F")
      (footprint "eagle-import:SOD323-W")
      (libsource (lib "eagle-import") (part "DIODE-SOD323-W"))
    )
    (comp (ref "D11")
      (value "C3D06065A")
      (footprint "eagle-import:TO220-2")
      (libsource (lib "eagle-import") (part "SCHOTTKY-TO220"))
    )
    (comp (ref "D12")
      (value "1N5819HW-7-F")
      (footprint "eagle-import:SOD323-W")
      (libsource (lib "eagle-import") (part "DIODE-SOD323-W"))
    )
    (comp (ref "D13")
      (value "1N5819HW-7-F")
      (footprint "eagle-import:SOD323-W")
      (libsource (lib "eagle-import") (part "DIODE-SOD323-W"))
    )
    (comp (ref "D14")
      (value "US1K-DIO")
      (footprint "eagle-import:DO214AA")
      (libsource (lib "eagle-import") (part "DIODEDO214AA"))
    )
    (comp (ref "D15")
      (value "C3D02065E")
      (footprint "eagle-import:TO252")
      (libsource (lib "eagle-import") (part "SCHOTTKY-SIC"))
    )
    (comp (ref "D16")
      (value "BAS316")
      (footprint "eagle-import:SOD323-R")
      (libsource (lib "eagle-import") (part "DIODESOD323R"))
    )
    (comp (ref "D17")
      (value "BAS316")
      (footprint "eagle-import:SOD323-R")
      (libsource (lib "eagle-import") (part "DIODESOD323R"))
    )
    (comp (ref "D18")
      (value "C3D02065E")
      (footprint "eagle-import:TO252")
      (libsource (lib "eagle-import") (part "SCHOTTKY-SIC"))
    )
    (comp (ref "D19")
      (value "N.C.")
      (footprint "eagle-import:SOD323-W")
      (libsource (lib "eagle-import") (part "DIODE-SOD323-W"))
    )
    (comp (ref "D20")
      (value "BAS316")
      (footprint "eagle-import:SOD323-R")
      (libsource (lib "eagle-import") (part "DIODESOD323R"))
    )
    (comp (ref "D21")
      (value "N.C.")
      (footprint "eagle-import:SOD323-W")
      (libsource (lib "eagle-import") (part "DIODE-SOD323-W"))
    )
    (comp (ref "D22")
      (value "BAS316")
      (footprint "eagle-import:SOD323-R")
      (libsource (lib "eagle-import") (part "DIODESOD323R"))
    )
    (comp (ref "D23")
      (value "BAS316")
      (footprint "eagle-import:SOD323-R")
      (libsource (lib "eagle-import") (part "DIODESOD323R"))
    )
    (comp (ref "D24")
      (value "BAS316")
      (footprint "eagle-import:SOD323-R")
      (libsource (lib "eagle-import") (part "DIODESOD323R"))
    )
    (comp (ref "IC2")
      (value "SI8233BB-D-IS1")
      (footprint "eagle-import:SOIC-16")
      (libsource (lib "eagle-import") (part "SI8233"))
    )
    (comp (ref "IC3")
      (value "LM5041B")
      (footprint "eagle-import:MTC16")
      (fields (field (name "MANUFACTURER_PART_NUMBER") "lm5041mtcnopb"))
      (libsource (lib "eagle-import") (part "LM5041"))
    )
    (comp (ref "IC4")
      (value "LM258D")
      (footprint "eagle-import:SOIC127P600X173-8N")
      (libsource (lib "eagle-import") (part "TL072SOIC8"))
    )
    (comp (ref "JP5")
      (value "JP2-NOCUT")
      (footprint "eagle-import:JP2-NOCUT")
      (libsource (lib "eagle-import") (part "JP2-NOCUT"))
    )
    (comp (ref "L6")
      (value "60B684C")
      (footprint "eagle-import:MURATA_6000B")
      (libsource (lib "eagle-import") (part "MURATA_6000B"))
    )
    (comp (ref "L7")
      (value "60B684C")
      (footprint "eagle-import:MURATA_6000B")
      (libsource (lib "eagle-import") (part "MURATA_6000B"))
    )
    (comp (ref "OK2")
      (value "TLP291-GB.SE-T")
      (footprint "eagle-import:SO4")
      (libsource (lib "eagle-import") (part "TLP291"))
    )
    (comp (ref "Q2")
      (value "C3M0280090D")
      (footprint "eagle-import:TO247BV")
      (libsource (lib "eagle-import") (part "IRFP240"))
    )
    (comp (ref "Q3")
      (value "C3M0280090D")
      (footprint "eagle-import:TO247BV")
      (libsource (lib "eagle-import") (part "IRFP240"))
    )
    (comp (ref "Q4")
      (value "NYC0102BLT1G")
      (footprint "eagle-import:SOT23")
      (libsource (lib "eagle-import") (part "NYC0102BLT1G"))
    )
    (comp (ref "Q5")
      (value "C3M0280090D")
      (footprint "eagle-import:TO247BV")
      (libsource (lib "eagle-import") (part "IRFP240"))
    )
    (comp (ref "Q6")
      (value "C3M0280090D")
      (footprint "eagle-import:TO247BV")
      (libsource (lib "eagle-import") (part "IRFP240"))
    )
    (comp (ref "R18")
      (value "10R")
      (footprint "eagle-import:R0805")
      (libsource (lib "eagle-import") (part "R-EU_R0805"))
    )
    (comp (ref "R19")
      (value "10K")
      (footprint "eagle-import:R0805")
      (libsource (lib "eagle-import") (part "R-EU_R0805"))
    )
    (comp (ref "R20")
      (value "33R")
      (footprint "eagle-import:R0805")
      (libsource (lib "eagle-import") (part "R-EU_R0805"))
    )
    (comp (ref "R21")
      (value "10R")
      (footprint "eagle-import:R0805")
      (libsource (lib "eagle-import") (part "R-EU_R0805"))
    )
    (comp (ref "R22")
      (value "100R")
      (footprint "eagle-import:R0805")
      (libsource (lib "eagle-import") (part "R-EU_R0805"))
    )
    (comp (ref "R23")
      (value "100R")
      (footprint "eagle-import:R0805")
      (libsource (lib "eagle-import") (part "R-EU_R0805"))
    )
    (comp (ref "R24")
      (value "22R/2-3W")
      (footprint "eagle-import:R2512")
      (libsource (lib "eagle-import") (part "R-EU_R2512"))
    )
    (comp (ref "R25")
      (value "22R/2-3W")
      (footprint "eagle-import:R2512")
      (libsource (lib "eagle-import") (part "R-EU_R2512"))
    )
    (comp (ref "R26")
      (value "1R")
      (footprint "eagle-import:R0805")
      (libsource (lib "eagle-import") (part "R-EU_R0805"))
    )
    (comp (ref "R27")
      (value "30K")
      (footprint "eagle-import:R0805")
      (libsource (lib "eagle-import") (part "R-EU_R0805"))
    )
    (comp (ref "R28")
      (value "33R")
      (footprint "eagle-import:R0805")
      (libsource (lib "eagle-import") (part "R-EU_R0805"))
    )
    (comp (ref "R29")
      (value "220K")
      (footprint "eagle-import:R1206")
      (libsource (lib "eagle-import") (part "R-EU_R1206"))
    )
    (comp (ref "R30")
      (value "10R")
      (footprint "eagle-import:R0805")
      (libsource (lib "eagle-import") (part "R-EU_R0805"))
    )
    (comp (ref "R31")
      (value "10R")
      (footprint "eagle-import:R0805")
      (libsource (lib "eagle-import") (part "R-EU_R0805"))
    )
    (comp (ref "R32")
      (value "47K")
      (footprint "eagle-import:R0805")
      (libsource (lib "eagle-import") (part "R-EU_R0805"))
    )
    (comp (ref "R33")
      (value "1R")
      (footprint "eagle-import:R0805")
      (libsource (lib "eagle-import") (part "R-EU_R0805"))
    )
    (comp (ref "R34")
      (value "22R/2-3W")
      (footprint "eagle-import:R2512")
      (libsource (lib "eagle-import") (part "R-EU_R2512"))
    )
    (comp (ref "R35")
      (value "1K")
      (footprint "eagle-import:R0805")
      (libsource (lib "eagle-import") (part "R-EU_R0805"))
    )
    (comp (ref "R36")
      (value "100K")
      (footprint "eagle-import:R0805")
      (libsource (lib "eagle-import") (part "R-EU_R0805"))
    )
    (comp (ref "R37")
      (value "22R/2-3W")
      (footprint "eagle-import:R2512")
      (libsource (lib "eagle-import") (part "R-EU_R2512"))
    )
    (comp (ref "R38")
      (value "10R")
      (footprint "eagle-import:R0805")
      (libsource (lib "eagle-import") (part "R-EU_R0805"))
    )
    (comp (ref "R39")
      (value "1K")
      (footprint "eagle-import:R0805")
      (libsource (lib "eagle-import") (part "R-EU_R0805"))
    )
    (comp (ref "R40")
      (value "10R")
      (footprint "eagle-import:R0805")
      (libsource (lib "eagle-import") (part "R-EU_R0805"))
    )
    (comp (ref "R41")
      (value "10K")
      (footprint "eagle-import:R0805")
      (libsource (lib "eagle-import") (part "R-EU_R0805"))
    )
    (comp (ref "R42")
      (value "30K")
      (footprint "eagle-import:R0805")
      (libsource (lib "eagle-import") (part "R-EU_R0805"))
    )
    (comp (ref "R43")
      (value "100K")
      (footprint "eagle-import:R0805")
      (libsource (lib "eagle-import") (part "R-EU_R0805"))
    )
    (comp (ref "R44")
      (value "33R")
      (footprint "eagle-import:R0805")
      (libsource (lib "eagle-import") (part "R-EU_R0805"))
    )
    (comp (ref "R45")
      (value "30K")
      (footprint "eagle-import:R0805")
      (libsource (lib "eagle-import") (part "R-EU_R0805"))
    )
    (comp (ref "R46")
      (value "82K")
      (footprint "eagle-import:R0805")
      (libsource (lib "eagle-import") (part "R-EU_R0805"))
    )
    (comp (ref "R47")
      (value "33R")
      (footprint "eagle-import:R0805")
      (libsource (lib "eagle-import") (part "R-EU_R0805"))
    )
    (comp (ref "R48")
      (value "1K")
      (footprint "eagle-import:R0805")
      (libsource (lib "eagle-import") (part "R-EU_R0805"))
    )
    (comp (ref "R49")
      (value "N.C.")
      (footprint "eagle-import:R0805")
      (libsource (lib "eagle-import") (part "R-EU_R0805"))
    )
    (comp (ref "R50")
      (value "6R2")
      (footprint "eagle-import:R0805")
      (libsource (lib "eagle-import") (part "R-EU_R0805"))
    )
    (comp (ref "R51")
      (value "4K7")
      (footprint "eagle-import:R0805")
      (libsource (lib "eagle-import") (part "R-EU_R0805"))
    )
    (comp (ref "R52")
      (value "750R")
      (footprint "eagle-import:R0805")
      (libsource (lib "eagle-import") (part "R-EU_R0805"))
    )
    (comp (ref "R53")
      (value "1K")
      (footprint "eagle-import:R0805")
      (libsource (lib "eagle-import") (part "R-EU_R0805"))
    )
    (comp (ref "R54")
      (value "8K2")
      (footprint "eagle-import:R0805")
      (libsource (lib "eagle-import") (part "R-EU_R0805"))
    )
    (comp (ref "R55")
      (value "4K7")
      (footprint "eagle-import:R0805")
      (libsource (lib "eagle-import") (part "R-EU_R0805"))
    )
    (comp (ref "R56")
      (value "5K6")
      (footprint "eagle-import:R0805")
      (libsource (lib "eagle-import") (part "R-EU_R0805"))
    )
    (comp (ref "R57")
      (value "47K")
      (footprint "eagle-import:R0805")
      (libsource (lib "eagle-import") (part "R-EU_R0805"))
    )
    (comp (ref "R58")
      (value "1K")
      (footprint "eagle-import:R0805")
      (libsource (lib "eagle-import") (part "R-EU_R0805"))
    )
    (comp (ref "R59")
      (value "30K")
      (footprint "eagle-import:R0805")
      (libsource (lib "eagle-import") (part "R-EU_R0805"))
    )
    (comp (ref "R60")
      (value "10K")
      (footprint "eagle-import:R0805")
      (libsource (lib "eagle-import") (part "R-EU_R0805"))
    )
    (comp (ref "R61")
      (value "1K")
      (footprint "eagle-import:R0805")
      (libsource (lib "eagle-import") (part "R-EU_R0805"))
    )
    (comp (ref "R62")
      (value "1K")
      (footprint "eagle-import:R0805")
      (libsource (lib "eagle-import") (part "R-EU_R0805"))
    )
    (comp (ref "SH1")
      (value "SHORTNOHOLE")
      (footprint "eagle-import:SHORT_NOHOLE")
      (libsource (lib "eagle-import") (part "SHORTNOHOLE"))
    )
    (comp (ref "TP2")
      (value "JUMPER-2PIN-2MM")
      (footprint "eagle-import:2MM-2")
      (libsource (lib "eagle-import") (part "JUMPER-2PIN-2MM"))
    )
    (comp (ref "TP3")
      (value "TEST-PIN1.2")
      (footprint "eagle-import:TEST-PIN_1.2MM")
      (libsource (lib "eagle-import") (part "TEST-PIN1.2"))
    )
    (comp (ref "TP4")
      (value "TEST-PIN1.2")
      (footprint "eagle-import:TEST-PIN_1.2MM")
      (libsource (lib "eagle-import") (part "TEST-PIN1.2"))
    )
    (comp (ref "TP5")
      (value "TEST-PIN1.2")
      (footprint "eagle-import:TEST-PIN_1.2MM")
      (libsource (lib "eagle-import") (part "TEST-PIN1.2"))
    )
    (comp (ref "TR2")
      (value "53100C")
      (footprint "eagle-import:MURATA_5300")
      (libsource (lib "eagle-import") (part "MURATA_5300"))
    )
    (comp (ref "TR3")
      (value "VAC T60006-L2025-W380")
      (footprint "eagle-import:VAC_DUAL_SEC")
      (libsource (lib "eagle-import") (part "PCB_TRAFO_FLYBACK2-VAC"))
    )
    (comp (ref "X3")
      (value "B2B-ZR")
      (footprint "eagle-import:B2B-ZR")
      (libsource (lib "eagle-import") (part "B2B-ZR"))
    )
    (comp (ref "ZD4")
      (value "MMSZ5V1T1G")
      (footprint "eagle-import:SOD323-W")
      (libsource (lib "eagle-import") (part "ZENER-DIODESOD323"))
    )
  )
  (nets
    (net (code "1") (name "+2.5VREF") (class "Default")
      (node (ref "C78") (pin "1") (pinfunction "1_1") (pintype "passive"))
      (node (ref "IC7") (pin "3") (pinfunction "+IN1_3") (pintype "input"))
      (node (ref "P1") (pin "E") (pinfunction "E_E") (pintype "passive"))
      (node (ref "R78") (pin "2") (pinfunction "2_2") (pintype "passive"))
      (node (ref "R84") (pin "1") (pinfunction "1_1") (pintype "passive"))
    )
    (net (code "2") (name "+5VREF") (class "Default")
      (node (ref "C45") (pin "2") (pinfunction "2_2") (pintype "passive"))
      (node (ref "IC3") (pin "4") (pinfunction "REF_4") (pintype "output"))
      (node (ref "R38") (pin "1") (pinfunction "1_1") (pintype "passive"))
      (node (ref "R49") (pin "1") (pinfunction "1_1") (pintype "passive"))
      (node (ref "R55") (pin "2") (pinfunction "2_2") (pintype "passive"))
      (node (ref "R56") (pin "2") (pinfunction "2_2") (pintype "passive"))
      (node (ref "X3") (pin "2") (pinfunction "1_2") (pintype "passive"))
    )
    (net (code "3") (name "+12V") (class "Default")
      (node (ref "C26") (pin "2") (pinfunction "2_2") (pintype "passive"))
      (node (ref "C27") (pin "2") (pinfunction "2_2") (pintype "passive"))
      (node (ref "C49") (pin "1") (pinfunction "1_1") (pintype "passive"))
      (node (ref "C50") (pin "1") (pinfunction "1_1") (pintype "passive"))
      (node (ref "IC4") (pin "8") (pinfunction "V+_8") (pintype "power_in"))
      (node (ref "JP1") (pin "2") (pinfunction "2_2") (pintype "passive"))
      (node (ref "OK2") (pin "1") (pinfunction "A_1") (pintype "passive"))
      (node (ref "R18") (pin "2") (pinfunction "2_2") (pintype "passive"))
      (node (ref "R30") (pin "2") (pinfunction "2_2") (pintype "passive"))
      (node (ref "R40") (pin "2") (pinfunction "2_2") (pintype "passive"))
    )
    (net (code "4") (name "0V") (class "Default")
      (node (ref "C13") (pin "-") (pinfunction "-_-") (pintype "passive"))
      (node (ref "C18") (pin "1") (pinfunction "1_1") (pintype "passive"))
      (node (ref "C21") (pin "2") (pinfunction "-_2") (pintype "passive"))
      (node (ref "C24") (pin "2") (pinfunction "2_2") (pintype "passive"))
      (node (ref "C25") (pin "2") (pinfunction "2_2") (pintype "passive"))
      (node (ref "C26") (pin "1") (pinfunction "1_1") (pintype "passive"))
      (node (ref "C27") (pin "1") (pinfunction "1_1") (pintype "passive"))
      (node (ref "C31") (pin "-") (pinfunction "-_-") (pintype "passive"))
      (node (ref "C32") (pin "-") (pinfunction "-_-") (pintype "passive"))
      (node (ref "C33") (pin "2") (pinfunction "2_2") (pintype "passive"))
      (node (ref "C35") (pin "2") (pinfunction "2_2") (pintype "passive"))
      (node (ref "C36") (pin "2") (pinfunction "2_2") (pintype "passive"))
      (node (ref "C37") (pin "2") (pinfunction "2_2") (pintype "passive"))
      (node (ref "C39") (pin "1") (pinfunction "1_1") (pintype "passive"))
      (node (ref "C41") (pin "2") (pinfunction "2_2") (pintype "passive"))
      (node (ref "C42") (pin "2") (pinfunction "2_2") (pintype "passive"))
      (node (ref "C6") (pin "2") (pinfunction "2_2") (pintype "passive"))
      (node (ref "C7") (pin "2") (pinfunction "-_2") (pintype "passive"))
      (node (ref "C8") (pin "2") (pinfunction "2_2") (pintype "passive"))
      (node (ref "D11") (pin "2") (pinfunction "A_2") (pintype "passive"))
      (node (ref "D8") (pin "A") (pinfunction "A_A") (pintype "passive"))
      (node (ref "IC1") (pin "1") (pinfunction "GND_1") (pintype "passive"))
      (node (ref "IC1") (pin "2") (pinfunction "GND_2") (pintype "passive"))
      (node (ref "IC1") (pin "3") (pinfunction "GND_3") (pintype "passive"))
      (node (ref "IC1") (pin "4") (pinfunction "GND_4") (pintype "passive"))
      (node (ref "IC2") (pin "9") (pinfunction "GNDB_9") (pintype "power_in"))
      (node (ref "JP4") (pin "NO") (pinfunction "NO_NO") (pintype "passive"))
      (node (ref "JP5") (pin "2") (pinfunction "2_2") (pintype "passive"))
      (node (ref "OK1") (pin "3") (pinfunction "EMIT_3") (pintype "passive"))
      (node (ref "Q3") (pin "S") (pinfunction "S_S") (pintype "passive"))
      (node (ref "Q5") (pin "S") (pinfunction "S_S") (pintype "passive"))
      (node (ref "Q6") (pin "S") (pinfunction "S_S") (pintype "passive"))
      (node (ref "R14") (pin "1") (pinfunction "1_1") (pintype "passive"))
      (node (ref "R15") (pin "2") (pinfunction "2_2") (pintype "passive"))
      (node (ref "R16") (pin "2") (pinfunction "2_2") (pintype "passive"))
      (node (ref "R32") (pin "2") (pinfunction "2_2") (pintype "passive"))
      (node (ref "R33") (pin "1") (pinfunction "1_1") (pintype "passive"))
      (node (ref "R33") (pin "2") (pinfunction "2_2") (pintype "passive"))
      (node (ref "SH1") (pin "P$2") (pinfunction "GND_B_P$2") (pintype "bidirectional"))
      (node (ref "TP3") (pin "1") (pinfunction "P$1_1") (pintype "bidirectional"))
      (node (ref "TP4") (pin "1") (pinfunction "P$1_1") (pintype "bidirectional"))
      (node (ref "TP5") (pin "1") (pinfunction "P$1_1") (pintype "bidirectional"))
      (node (ref "TR1") (pin "6") (pinfunction "S_BIAS_6") (pintype "passive"))
      (node (ref "ZD1") (pin "A") (pinfunction "A_A") (pintype "passive"))
      (node (ref "ZD2") (pin "A") (pinfunction "A_A") (pintype "passive"))
    )
    (net (code "5") (name "AC_L_IN") (class "Default")
      (node (ref "C1") (pin "2") (pinfunction "2_2") (pintype "passive"))
      (node (ref "C5A") (pin "2") (pinfunction "2_2") (pintype "passive"))
      (node (ref "L1") (pin "2") (pinfunction "2_2") (pintype "passive"))
      (node (ref "R2") (pin "2") (pinfunction "2_2") (pintype "passive"))
      (node (ref "SAR2") (pin "1") (pinfunction "P$1_1") (pintype "bidirectional"))
      (node (ref "X1") (pin "1") (pinfunction "1_1") (pintype "passive"))
    )
    (net (code "6") (name "AC_N_IN") (class "Default")
      (node (ref "C1") (pin "1") (pinfunction "1_1") (pintype "passive"))
      (node (ref "C4A") (pin "2") (pinfunction "2_2") (pintype "passive"))
      (node (ref "L1") (pin "4") (pinfunction "2_4") (pintype "passive"))
      (node (ref "R1") (pin "1") (pinfunction "1_1") (pintype "passive"))
      (node (ref "SAR1") (pin "1") (pinfunction "P$1_1") (pintype "bidirectional"))
      (node (ref "X1") (pin "2") (pinfunction "1_2") (pintype "passive"))
    )
    (net (code "7") (name "AGND") (class "Default")
      (node (ref "C34") (pin "1") (pinfunction "1_1") (pintype "passive"))
      (node (ref "C40") (pin "2") (pinfunction "2_2") (pintype "passive"))
      (node (ref "C43") (pin "1") (pinfunction "1_1") (pintype "passive"))
      (node (ref "C44") (pin "2") (pinfunction "2_2") (pintype "passive"))
      (node (ref "C45") (pin "1") (pinfunction "1_1") (pintype "passive"))
      (node (ref "C46") (pin "1") (pinfunction "1_1") (pintype "passive"))
      (node (ref "C47") (pin "1") (pinfunction "1_1") (pintype "passive"))
      (node (ref "C48") (pin "2") (pinfunction "2_2") (pintype "passive"))
      (node (ref "C49") (pin "2") (pinfunction "2_2") (pintype "passive"))
      (node (ref "C51") (pin "2") (pinfunction "2_2") (pintype "passive"))
      (node (ref "C52") (pin "1") (pinfunction "1_1") (pintype "passive"))
      (node (ref "C53") (pin "1") (pinfunction "1_1") (pintype "passive"))
      (node (ref "IC2") (pin "4") (pinfunction "GNDI_4") (pintype "power_in"))
      (node (ref "IC2") (pin "5") (pinfunction "DISABLE_5") (pintype "input"))
      (node (ref "IC3") (pin "10") (pinfunction "PGND_10") (pintype "power_in"))
      (node (ref "IC3") (pin "11") (pinfunction "AGND_11") (pintype "power_in"))
      (node (ref "IC4") (pin "4") (pinfunction "V-_4") (pintype "power_in"))
      (node (ref "JP5") (pin "1") (pinfunction "1_1") (pintype "passive"))
      (node (ref "OK3") (pin "3") (pinfunction "EMIT_3") (pintype "passive"))
      (node (ref "Q4") (pin "1") (pinfunction "C_1") (pintype "passive"))
      (node (ref "R26") (pin "1") (pinfunction "1_1") (pintype "passive"))
      (node (ref "R26") (pin "2") (pinfunction "2_2") (pintype "passive"))
      (node (ref "R27") (pin "1") (pinfunction "1_1") (pintype "passive"))
      (node (ref "R41") (pin "2") (pinfunction "2_2") (pintype "passive"))
      (node (ref "R45") (pin "2") (pinfunction "2_2") (pintype "passive"))
      (node (ref "R46") (pin "2") (pinfunction "2_2") (pintype "passive"))
      (node (ref "R52") (pin "2") (pinfunction "2_2") (pintype "passive"))
      (node (ref "R53") (pin "2") (pinfunction "2_2") (pintype "passive"))
      (node (ref "R54") (pin "1") (pinfunction "1_1") (pintype "passive"))
      (node (ref "R58") (pin "2") (pinfunction "2_2") (pintype "passive"))
      (node (ref "R59") (pin "2") (pinfunction "2_2") (pintype "passive"))
      (node (ref "R60") (pin "2") (pinfunction "2_2") (pintype "passive"))
      (node (ref "R61") (pin "2") (pinfunction "2_2") (pintype "passive"))
      (node (ref "R62") (pin "2") (pinfunction "2_2") (pintype "passive"))
      (node (ref "ZD4") (pin "A") (pinfunction "A_A") (pintype "passive"))
    )
    (net (code "8") (name "AUX_AC") (class "Default")
      (node (ref "C3") (pin "2") (pinfunction "2_2") (pintype "passive"))
      (node (ref "D1") (pin "A") (pinfunction "A_A") (pintype "passive"))
      (node (ref "D6") (pin "A") (pinfunction "A_A") (pintype "passive"))
      (node (ref "D7") (pin "A") (pinfunction "A_A") (pintype "passive"))
      (node (ref "R11") (pin "2") (pinfunction "2_2") (pintype "passive"))
      (node (ref "TR1") (pin "7") (pinfunction "S_BIAS_DOT_7") (pintype "passive"))
    )
    (net (code "9") (name "BUCK_OUT") (class "Default")
      (node (ref "C28") (pin "2") (pinfunction "2_2") (pintype "passive"))
      (node (ref "C29") (pin "2") (pinfunction "2_2") (pintype "passive"))
      (node (ref "C30") (pin "2") (pinfunction "2_2") (pintype "passive"))
      (node (ref "D11") (pin "1") (pinfunction "C_1") (pintype "passive"))
      (node (ref "IC2") (pin "14") (pinfunction "GNDA_14") (pintype "power_in"))
      (node (ref "L6") (pin "2") (pinfunction "P$2_2") (pintype "bidirectional"))
      (node (ref "L7") (pin "2") (pinfunction "P$2_2") (pintype "bidirectional"))
      (node (ref "Q2") (pin "S") (pinfunction "S_S") (pintype "passive"))
      (node (ref "Q3") (pin "D") (pinfunction "D_D") (pintype "passive"))
    )
    (net (code "10") (name "COMP") (class "Default")
      (node (ref "C47") (pin "2") (pinfunction "2_2") (pintype "passive"))
      (node (ref "IC3") (pin "3") (pinfunction "COMP_3") (pintype "passive"))
      (node (ref "JP9") (pin "1") (pinfunction "1_1") (pintype "passive"))
      (node (ref "R49") (pin "2") (pinfunction "2_2") (pintype "passive"))
      (node (ref "R54") (pin "2") (pinfunction "2_2") (pintype "passive"))
    )
    (net (code "11") (name "CT_OUT+") (class "Default")
      (node (ref "D20") (pin "A") (pinfunction "A_A") (pintype "passive"))
      (node (ref "R19") (pin "1") (pinfunction "1_1") (pintype "passive"))
      (node (ref "TR2") (pin "3") (pinfunction "S_3") (pintype "passive"))
    )
    (net (code "12") (name "CT_OUT-") (class "Default")
      (node (ref "R19") (pin "2") (pinfunction "2_2") (pintype "passive"))
      (node (ref "R50") (pin "2") (pinfunction "2_2") (pintype "passive"))
      (node (ref "R53") (pin "1") (pinfunction "1_1") (pintype "passive"))
      (node (ref "TR2") (pin "1") (pinfunction "S_DOT_1") (pintype "passive"))
    )
    (net (code "13") (name "DC_BUS") (class "Default")
      (node (ref "B1") (pin "+") (pinfunction "+_+") (pintype "passive"))
      (node (ref "C31") (pin "+") (pinfunction "+_+") (pintype "passive"))
      (node (ref "C32") (pin "+") (pinfunction "+_+") (pintype "passive"))
      (node (ref "C33") (pin "1") (pinfunction "1_1") (pintype "passive"))
      (node (ref "D14") (pin "C") (pinfunction "C_C") (pintype "passive"))
      (node (ref "JP2") (pin "1") (pinfunction "1_1") (pintype "passive"))
      (node (ref "L3") (pin "P$1") (pinfunction "1_P$1") (pintype "passive"))
      (node (ref "R29") (pin "1") (pinfunction "1_1") (pintype "passive"))
      (node (ref "TR2") (pin "7") (pinfunction "P_7") (pintype "passive"))
    )
    (net (code "14") (name "DC_OUT") (class "Default")
      (node (ref "C11") (pin "1") (pinfunction "1_1") (pintype "passive"))
      (node (ref "L2") (pin "2") (pinfunction "2_2") (pintype "passive"))
      (node (ref "X2") (pin "8") (pinfunction "1_8") (pintype "passive"))
    )
    (net (code "15") (name "FB") (class "Default")
      (node (ref "C48") (pin "1") (pinfunction "1_1") (pintype "passive"))
      (node (ref "IC3") (pin "2") (pinfunction "FB_2") (pintype "input"))
      (node (ref "R42") (pin "1") (pinfunction "1_1") (pintype "passive"))
      (node (ref "R52") (pin "1") (pinfunction "1_1") (pintype "passive"))
      (node (ref "R57") (pin "1") (pinfunction "1_1") (pintype "passive"))
    )
    (net (code "16") (name "GND") (class "Default")
      (node (ref "C14") (pin "1") (pinfunction "+_1") (pintype "passive"))
      (node (ref "C15") (pin "1") (pinfunction "1_1") (pintype "passive"))
      (node (ref "C17") (pin "2") (pinfunction "2_2") (pintype "passive"))
      (node (ref "C20") (pin "-") (pinfunction "-_-") (pintype "passive"))
      (node (ref "C22") (pin "2") (pinfunction "2_2") (pintype "passive"))
      (node (ref "C54") (pin "-") (pinfunction "-_-") (pintype "passive"))
      (node (ref "C55") (pin "-") (pinfunction "-_-") (pintype "passive"))
      (node (ref "C56") (pin "-") (pinfunction "-_-") (pintype "passive"))
      (node (ref "C57") (pin "2") (pinfunction "2_2") (pintype "passive"))
      (node (ref "C58") (pin "-") (pinfunction "-_-") (pintype "passive"))
      (node (ref "C59") (pin "-") (pinfunction "-_-") (pintype "passive"))
      (node (ref "C60") (pin "2") (pinfunction "2_2") (pintype "passive"))
      (node (ref "C61") (pin "2") (pinfunction "2_2") (pintype "passive"))
      (node (ref "C62") (pin "1") (pinfunction "1_1") (pintype "passive"))
      (node (ref "C63") (pin "2") (pinfunction "2_2") (pintype "passive"))
      (node (ref "C64") (pin "2") (pinfunction "2_2") (pintype "passive"))
      (node (ref "C65") (pin "2") (pinfunction "2_2") (pintype "passive"))
      (node (ref "C68") (pin "1") (pinfunction "1_1") (pintype "passive"))
      (node (ref "C69") (pin "2") (pinfunction "2_2") (pintype "passive"))
      (node (ref "C70") (pin "2") (pinfunction "2_2") (pintype "passive"))
      (node (ref "C72") (pin "2") (pinfunction "2_2") (pintype "passive"))
      (node (ref "C74") (pin "2") (pinfunction "2_2") (pintype "passive"))
      (node (ref "C77") (pin "-") (pinfunction "-_-") (pintype "passive"))
      (node (ref "C78") (pin "2") (pinfunction "2_2") (pintype "passive"))
      (node (ref "C79") (pin "2") (pinfunction "2_2") (pintype "passive"))
      (node (ref "IC5") (pin "6") (pinfunction "VS_6") (pintype "passive"))
      (node (ref "IC5") (pin "7") (pinfunction "GND_7") (pintype "power_in"))
      (node (ref "IC6") (pin "3") (pinfunction "+IN_3") (pintype "input"))
      (node (ref "IC6") (pin "5") (pinfunction "+IN_5") (pintype "input"))
      (node (ref "IC7") (pin "4") (pinfunction "VCC-_4") (pintype "power_in"))
      (node (ref "JP3") (pin "NO") (pinfunction "NO_NO") (pintype "passive"))
      (node (ref "LED1") (pin "TC") (pinfunction "C_TC") (pintype "passive"))
      (node (ref "OK2") (pin "3") (pinfunction "EMIT_3") (pintype "passive"))
      (node (ref "P1") (pin "A") (pinfunction "A_A") (pintype "passive"))
      (node (ref "Q7") (pin "2") (pinfunction "S_2") (pintype "passive"))
      (node (ref "Q8") (pin "2") (pinfunction "S_2") (pintype "passive"))
      (node (ref "R67") (pin "1") (pinfunction "1_1") (pintype "passive"))
      (node (ref "R70") (pin "2") (pinfunction "2_2") (pintype "passive"))
      (node (ref "TP1") (pin "1") (pinfunction "P$1_1") (pintype "bidirectional"))
      (node (ref "TP6") (pin "GND") (pinfunction "GND_GND") (pintype "bidirectional"))
      (node (ref "TR1") (pin "10") (pinfunction "S1_10") (pintype "passive"))
      (node (ref "TR1") (pin "11") (pinfunction "S1_11") (pintype "passive"))
      (node (ref "TR1") (pin "9") (pinfunction "S2_DOT_9") (pintype "passive"))
      (node (ref "X2") (pin "2") (pinfunction "1_2") (pintype "passive"))
      (node (ref "X2") (pin "6") (pinfunction "1_6") (pintype "passive"))
      (node (ref "X4") (pin "2") (pinfunction "1_2") (pintype "passive"))
      (node (ref "ZD3") (pin "A") (pinfunction "A_A") (pintype "passive"))
      (node (ref "ZD5") (pin "A") (pinfunction "A_A") (pintype "passive"))
    )
    (net (code "17") (name "GNDA") (class "Default")
      (node (ref "B1") (pin "-") (pinfunction "-_-") (pintype "passive"))
      (node (ref "SH1") (pin "P$1") (pinfunction "GND_A_P$1") (pintype "bidirectional"))
    )
    (net (code "18") (name "HD") (class "Default")
      (node (ref "IC3") (pin "5") (pinfunction "HD_5") (pintype "output"))
      (node (ref "R22") (pin "2") (pinfunction "2_2") (pintype "passive"))
    )
    (net (code "19") (name "HI_OUT") (class "Default")
      (node (ref "IC2") (pin "15") (pinfunction "VOA_15") (pintype "output"))
      (node (ref "R20") (pin "2") (pinfunction "2_2") (pintype "passive"))
      (node (ref "R21") (pin "2") (pinfunction "2_2") (pintype "passive"))
    )
    (net (code "20") (name "LD") (class "Default")
      (node (ref "IC3") (pin "6") (pinfunction "LD_6") (pintype "output"))
      (node (ref "R23") (pin "2") (pinfunction "2_2") (pintype "passive"))
    )
    (net (code "21") (name "LO_OUT") (class "Default")
      (node (ref "IC2") (pin "10") (pinfunction "VOB_10") (pintype "output"))
      (node (ref "R28") (pin "1") (pinfunction "1_1") (pintype "passive"))
      (node (ref "R31") (pin "1") (pinfunction "1_1") (pintype "passive"))
    )
    (net (code "22") (name "Net-(C3-Pad1)") (class "Default")
      (node (ref "C3") (pin "1") (pinfunction "1_1") (pintype "passive"))
      (node (ref "R3") (pin "2") (pinfunction "2_2") (pintype "passive"))
    )
    (net (code "23") (name "Net-(C6-Pad1)") (class "Default")
      (node (ref "C6") (pin "1") (pinfunction "1_1") (pintype "passive"))
      (node (ref "JP1") (pin "1") (pinfunction "1_1") (pintype "passive"))
      (node (ref "Q1") (pin "E") (pinfunction "E_E") (pintype "passive"))
    )
    (net (code "24") (name "Net-(C7-+)") (class "Default")
      (node (ref "C7") (pin "1") (pinfunction "+_1") (pintype "passive"))
      (node (ref "D1") (pin "C") (pinfunction "C_C") (pintype "passive"))
      (node (ref "Q1") (pin "C") (pinfunction "C_C") (pintype "passive"))
      (node (ref "R3") (pin "1") (pinfunction "1_1") (pintype "passive"))
      (node (ref "R4") (pin "1") (pinfunction "1_1") (pintype "passive"))
    )
    (net (code "25") (name "Net-(C8-Pad1)") (class "Default")
      (node (ref "C8") (pin "1") (pinfunction "1_1") (pintype "passive"))
      (node (ref "Q1") (pin "B") (pinfunction "B_B") (pintype "passive"))
      (node (ref "R4") (pin "2") (pinfunction "2_2") (pintype "passive"))
      (node (ref "ZD1") (pin "C") (pinfunction "C_C") (pintype "passive"))
    )
    (net (code "26") (name "Net-(C9-Pad1)") (class "Default")
      (node (ref "C9") (pin "1") (pinfunction "1_1") (pintype "passive"))
      (node (ref "R5") (pin "2") (pinfunction "2_2") (pintype "passive"))
    )
    (net (code "27") (name "Net-(C10-+)") (class "Default")
      (node (ref "C10") (pin "1") (pinfunction "+_1") (pintype "passive"))
      (node (ref "D2") (pin "C") (pinfunction "C_C") (pintype "passive"))
      (node (ref "L2") (pin "1") (pinfunction "1_1") (pintype "passive"))
      (node (ref "R5") (pin "1") (pinfunction "1_1") (pintype "passive"))
    )
    (net (code "28") (name "Net-(C10--)") (class "Default")
      (node (ref "C10") (pin "2") (pinfunction "-_2") (pintype "passive"))
      (node (ref "C11") (pin "2") (pinfunction "2_2") (pintype "passive"))
      (node (ref "JP3") (pin "COM") (pinfunction "COM_COM") (pintype "passive"))
      (node (ref "TR1") (pin "14") (pinfunction "S3_14") (pintype "passive"))
      (node (ref "X2") (pin "7") (pinfunction "1_7") (pintype "passive"))
    )
    (net (code "29") (name "Net-(C12-Pad2)") (class "Default")
      (node (ref "C12") (pin "2") (pinfunction "2_2") (pintype "passive"))
      (node (ref "D3") (pin "C") (pinfunction "C_C") (pintype "passive"))
      (node (ref "R6") (pin "2") (pinfunction "2_2") (pintype "passive"))
    )
    (net (code "30") (name "Net-(C14--)") (class "Default")
      (node (ref "C14") (pin "2") (pinfunction "-_2") (pintype "passive"))
      (node (ref "D4") (pin "A") (pinfunction "A_A") (pintype "passive"))
      (node (ref "L4") (pin "1") (pinfunction "1_1") (pintype "passive"))
      (node (ref "R9") (pin "1") (pinfunction "1_1") (pintype "passive"))
    )
    (net (code "31") (name "Net-(C16-Pad1)") (class "Default")
      (node (ref "C16") (pin "1") (pinfunction "1_1") (pintype "passive"))
      (node (ref "R9") (pin "2") (pinfunction "2_2") (pintype "passive"))
    )
    (net (code "32") (name "Net-(C17-Pad1)") (class "Default")
      (node (ref "C17") (pin "1") (pinfunction "1_1") (pintype "passive"))
      (node (ref "JP4") (pin "COM") (pinfunction "COM_COM") (pintype "passive"))
    )
    (net (code "33") (name "Net-(C19-Pad1)") (class "Default")
      (node (ref "C19") (pin "1") (pinfunction "1_1") (pintype "passive"))
      (node (ref "R10") (pin "2") (pinfunction "2_2") (pintype "passive"))
    )
    (net (code "34") (name "Net-(C19-Pad2)") (class "Default")
      (node (ref "C19") (pin "2") (pinfunction "2_2") (pintype "passive"))
      (node (ref "D5") (pin "A") (pinfunction "A_A") (pintype "passive"))
      (node (ref "TR1") (pin "12") (pinfunction "S1_DOT_12") (pintype "passive"))
      (node (ref "TR1") (pin "13") (pinfunction "S1_DOT_13") (pintype "passive"))
    )
    (net (code "35") (name "Net-(C20-Pad+)") (class "Default")
      (node (ref "C20") (pin "+") (pinfunction "+_+") (pintype "passive"))
      (node (ref "D5") (pin "C") (pinfunction "C_C") (pintype "passive"))
      (node (ref "L5") (pin "1") (pinfunction "1_1") (pintype "passive"))
      (node (ref "R10") (pin "1") (pinfunction "1_1") (pintype "passive"))
      (node (ref "R13") (pin "1") (pinfunction "1_1") (pintype "passive"))
    )
    (net (code "36") (name "Net-(C21-+)") (class "Default")
      (node (ref "C18") (pin "2") (pinfunction "2_2") (pintype "passive"))
      (node (ref "C21") (pin "1") (pinfunction "+_1") (pintype "passive"))
      (node (ref "D6") (pin "C") (pinfunction "C_C") (pintype "passive"))
      (node (ref "IC1") (pin "5") (pinfunction "VDD_5") (pintype "power_in"))
      (node (ref "ZD2") (pin "C") (pinfunction "C_C") (pintype "passive"))
    )
    (net (code "37") (name "Net-(C23-Pad1)") (class "Default")
      (node (ref "C23") (pin "1") (pinfunction "1_1") (pintype "passive"))
      (node (ref "R16") (pin "1") (pinfunction "1_1") (pintype "passive"))
    )
    (net (code "38") (name "Net-(C38-Pad1)") (class "Default")
      (node (ref "C38") (pin "1") (pinfunction "1_1") (pintype "passive"))
      (node (ref "R25") (pin "1") (pinfunction "1_1") (pintype "passive"))
    )
    (net (code "39") (name "Net-(C39-Pad2)") (class "Default")
      (node (ref "C39") (pin "2") (pinfunction "2_2") (pintype "passive"))
      (node (ref "D15") (pin "1") (pinfunction "C_1") (pintype "passive"))
      (node (ref "D15") (pin "3") (pinfunction "C_3") (pintype "passive"))
      (node (ref "D18") (pin "1") (pinfunction "C_1") (pintype "passive"))
      (node (ref "D18") (pin "3") (pinfunction "C_3") (pintype "passive"))
      (node (ref "R34") (pin "1") (pinfunction "1_1") (pintype "passive"))
      (node (ref "R37") (pin "1") (pinfunction "1_1") (pintype "passive"))
      (node (ref "R43") (pin "2") (pinfunction "2_2") (pintype "passive"))
    )
    (net (code "40") (name "Net-(C50-Pad2)") (class "Default")
      (node (ref "C50") (pin "2") (pinfunction "2_2") (pintype "passive"))
      (node (ref "D23") (pin "A") (pinfunction "A_A") (pintype "passive"))
      (node (ref "R62") (pin "1") (pinfunction "1_1") (pintype "passive"))
    )
    (net (code "41") (name "Net-(C62-Pad2)") (class "Default")
      (node (ref "C62") (pin "2") (pinfunction "2_2") (pintype "passive"))
      (node (ref "R64") (pin "1") (pinfunction "1_1") (pintype "passive"))
    )
    (net (code "42") (name "Net-(C63-Pad1)") (class "Default")
      (node (ref "C63") (pin "1") (pinfunction "1_1") (pintype "passive"))
      (node (ref "R65") (pin "2") (pinfunction "2_2") (pintype "passive"))
      (node (ref "R66") (pin "2") (pinfunction "2_2") (pintype "passive"))
    )
    (net (code "43") (name "Net-(C69-Pad1)") (class "Default")
      (node (ref "C69") (pin "1") (pinfunction "1_1") (pintype "passive"))
      (node (ref "R72") (pin "2") (pinfunction "2_2") (pintype "passive"))
      (node (ref "R73") (pin "2") (pinfunction "2_2") (pintype "passive"))
    )
    (net (code "44") (name "Net-(C71-Pad2)") (class "Default")
      (node (ref "C71") (pin "2") (pinfunction "2_2") (pintype "passive"))
      (node (ref "R80") (pin "2") (pinfunction "2_2") (pintype "passive"))
    )
    (net (code "45") (name "Net-(C76-Pad2)") (class "Default")
      (node (ref "C76") (pin "2") (pinfunction "2_2") (pintype "passive"))
      (node (ref "R83") (pin "2") (pinfunction "2_2") (pintype "passive"))
    )
    (net (code "46") (name "Net-(C77-Pad+)") (class "Default")
      (node (ref "C77") (pin "+") (pinfunction "+_+") (pintype "passive"))
      (node (ref "R82") (pin "1") (pinfunction "1_1") (pintype "passive"))
      (node (ref "R88") (pin "1") (pinfunction "1_1") (pintype "passive"))
      (node (ref "R89") (pin "1") (pinfunction "1_1") (pintype "passive"))
    )
    (net (code "47") (name "Net-(D7-PadC)") (class "Default")
      (node (ref "D7") (pin "C") (pinfunction "C_C") (pintype "passive"))
      (node (ref "D8") (pin "C") (pinfunction "C_C") (pintype "passive"))
      (node (ref "R12") (pin "2") (pinfunction "2_2") (pintype "passive"))
    )
    (net (code "48") (name "Net-(D9-A)") (class "Default")
      (node (ref "D9") (pin "2") (pinfunction "A_2") (pintype "passive"))
      (node (ref "R18") (pin "1") (pinfunction "1_1") (pintype "passive"))
    )
    (net (code "49") (name "Net-(D10-PadA)") (class "Default")
      (node (ref "D10") (pin "A") (pinfunction "A_A") (pintype "passive"))
      (node (ref "Q2") (pin "G") (pinfunction "G_G") (pintype "passive"))
      (node (ref "R20") (pin "1") (pinfunction "1_1") (pintype "passive"))
    )
    (net (code "50") (name "Net-(D10-PadC)") (class "Default")
      (node (ref "D10") (pin "C") (pinfunction "C_C") (pintype "passive"))
      (node (ref "R21") (pin "1") (pinfunction "1_1") (pintype "passive"))
    )
    (net (code "51") (name "Net-(D12-PadA)") (class "Default")
      (node (ref "D12") (pin "A") (pinfunction "A_A") (pintype "passive"))
      (node (ref "R30") (pin "1") (pinfunction "1_1") (pintype "passive"))
    )
    (net (code "52") (name "Net-(D13-PadA)") (class "Default")
      (node (ref "D13") (pin "A") (pinfunction "A_A") (pintype "passive"))
      (node (ref "Q3") (pin "G") (pinfunction "G_G") (pintype "passive"))
      (node (ref "R28") (pin "2") (pinfunction "2_2") (pintype "passive"))
      (node (ref "R32") (pin "1") (pinfunction "1_1") (pintype "passive"))
    )
    (net (code "53") (name "Net-(D13-PadC)") (class "Default")
      (node (ref "D13") (pin "C") (pinfunction "C_C") (pintype "passive"))
      (node (ref "R31") (pin "2") (pinfunction "2_2") (pintype "passive"))
    )
    (net (code "54") (name "Net-(D14-PadA)") (class "Default")
      (node (ref "D14") (pin "A") (pinfunction "A_A") (pintype "passive"))
      (node (ref "R34") (pin "2") (pinfunction "2_2") (pintype "passive"))
      (node (ref "R37") (pin "2") (pinfunction "2_2") (pintype "passive"))
    )
    (net (code "55") (name "Net-(D15-A)") (class "Default")
      (node (ref "D15") (pin "2") (pinfunction "A_2") (pintype "passive"))
      (node (ref "L6") (pin "1") (pinfunction "P$1_1") (pintype "bidirectional"))
      (node (ref "Q5") (pin "D") (pinfunction "D_D") (pintype "passive"))
      (node (ref "R24") (pin "2") (pinfunction "2_2") (pintype "passive"))
      (node (ref "TR3") (pin "P1") (pinfunction "P_P1") (pintype "passive"))
    )
    (net (code "56") (name "Net-(D16-PadA)") (class "Default")
      (node (ref "D16") (pin "A") (pinfunction "A_A") (pintype "passive"))
      (node (ref "R35") (pin "2") (pinfunction "2_2") (pintype "passive"))
    )
    (net (code "57") (name "Net-(D17-PadA)") (class "Default")
      (node (ref "D17") (pin "A") (pinfunction "A_A") (pintype "passive"))
      (node (ref "R36") (pin "2") (pinfunction "2_2") (pintype "passive"))
      (node (ref "R39") (pin "2") (pinfunction "2_2") (pintype "passive"))
      (node (ref "R41") (pin "1") (pinfunction "1_1") (pintype "passive"))
      (node (ref "TP2") (pin "2") (pinfunction "2_2") (pintype "passive"))
    )
    (net (code "58") (name "Net-(D18-A)") (class "Default")
      (node (ref "C38") (pin "2") (pinfunction "2_2") (pintype "passive"))
      (node (ref "D18") (pin "2") (pinfunction "A_2") (pintype "passive"))
      (node (ref "L7") (pin "1") (pinfunction "P$1_1") (pintype "bidirectional"))
      (node (ref "Q6") (pin "D") (pinfunction "D_D") (pintype "passive"))
      (node (ref "TR3") (pin "P1_DOT") (pinfunction "P_DOT_P1_DOT") (pintype "passive"))
    )
    (net (code "59") (name "Net-(D19-PadC)") (class "Default")
      (node (ref "D19") (pin "C") (pinfunction "C_C") (pintype "passive"))
      (node (ref "Q5") (pin "G") (pinfunction "G_G") (pintype "passive"))
      (node (ref "R44") (pin "1") (pinfunction "1_1") (pintype "passive"))
    )
    (net (code "60") (name "Net-(D20-PadC)") (class "Default")
      (node (ref "D20") (pin "C") (pinfunction "C_C") (pintype "passive"))
      (node (ref "R48") (pin "1") (pinfunction "1_1") (pintype "passive"))
      (node (ref "R50") (pin "1") (pinfunction "1_1") (pintype "passive"))
    )
    (net (code "61") (name "Net-(D21-PadC)") (class "Default")
      (node (ref "D21") (pin "C") (pinfunction "C_C") (pintype "passive"))
      (node (ref "Q6") (pin "G") (pinfunction "G_G") (pintype "passive"))
      (node (ref "R47") (pin "1") (pinfunction "1_1") (pintype "passive"))
    )
    (net (code "62") (name "Net-(D22-PadC)") (class "Default")
      (node (ref "D22") (pin "C") (pinfunction "C_C") (pintype "passive"))
      (node (ref "D24") (pin "C") (pinfunction "C_C") (pintype "passive"))
      (node (ref "R51") (pin "2") (pinfunction "2_2") (pintype "passive"))
      (node (ref "R58") (pin "1") (pinfunction "1_1") (pintype "passive"))
    )
    (net (code "63") (name "Net-(IC1-BR)") (class "Default")
      (node (ref "IC1") (pin "8") (pinfunction "BR_8") (pintype "input"))
      (node (ref "R15") (pin "1") (pinfunction "1_1") (pintype "passive"))
      (node (ref "R8") (pin "2") (pinfunction "2_2") (pintype "passive"))
    )
    (net (code "64") (name "Net-(IC1-FB)") (class "Default")
      (node (ref "C23") (pin "2") (pinfunction "2_2") (pintype "passive"))
      (node (ref "C25") (pin "1") (pinfunction "1_1") (pintype "passive"))
      (node (ref "IC1") (pin "7") (pinfunction "FB_7") (pintype "input"))
      (node (ref "OK1") (pin "4") (pinfunction "COL_4") (pintype "passive"))
    )
    (net (code "65") (name "Net-(IC1-ZCD)") (class "Default")
      (node (ref "C24") (pin "1") (pinfunction "1_1") (pintype "passive"))
      (node (ref "IC1") (pin "6") (pinfunction "ZCD_6") (pintype "input"))
      (node (ref "R11") (pin "1") (pinfunction "1_1") (pintype "passive"))
      (node (ref "R12") (pin "1") (pinfunction "1_1") (pintype "passive"))
      (node (ref "R14") (pin "2") (pinfunction "2_2") (pintype "passive"))
    )
    (net (code "66") (name "Net-(IC2-DT)") (class "Default")
      (node (ref "IC2") (pin "6") (pinfunction "DT_6") (pintype "input"))
      (node (ref "R27") (pin "2") (pinfunction "2_2") (pintype "passive"))
    )
    (net (code "67") (name "Net-(IC2-VDDA)") (class "Default")
      (node (ref "C28") (pin "1") (pinfunction "1_1") (pintype "passive"))
      (node (ref "C29") (pin "1") (pinfunction "1_1") (pintype "passive"))
      (node (ref "C30") (pin "1") (pinfunction "1_1") (pintype "passive"))
      (node (ref "D9") (pin "1") (pinfunction "C_1") (pintype "passive"))
      (node (ref "D9") (pin "3") (pinfunction "C_3") (pintype "passive"))
      (node (ref "IC2") (pin "16") (pinfunction "VDDA_16") (pintype "power_in"))
    )
    (net (code "68") (name "Net-(IC2-VDDB)") (class "Default")
      (node (ref "C35") (pin "1") (pinfunction "1_1") (pintype "passive"))
      (node (ref "C36") (pin "1") (pinfunction "1_1") (pintype "passive"))
      (node (ref "C37") (pin "1") (pinfunction "1_1") (pintype "passive"))
      (node (ref "D12") (pin "C") (pinfunction "C_C") (pintype "passive"))
      (node (ref "IC2") (pin "11") (pinfunction "VDDB_11") (pintype "power_in"))
    )
    (net (code "69") (name "Net-(IC2-VIA)") (class "Default")
      (node (ref "IC2") (pin "1") (pinfunction "VIA_1") (pintype "input"))
      (node (ref "R22") (pin "1") (pinfunction "1_1") (pintype "passive"))
    )
    (net (code "70") (name "Net-(IC2-VIB)") (class "Default")
      (node (ref "IC2") (pin "2") (pinfunction "VIB_2") (pintype "input"))
      (node (ref "R23") (pin "1") (pinfunction "1_1") (pintype "passive"))
    )
    (net (code "71") (name "Net-(IC3-CS)") (class "Default")
      (node (ref "C46") (pin "2") (pinfunction "2_2") (pintype "passive"))
      (node (ref "IC3") (pin "12") (pinfunction "CS_12") (pintype "input"))
      (node (ref "R48") (pin "2") (pinfunction "2_2") (pintype "passive"))
    )
    (net (code "72") (name "Net-(IC3-RT{slash}SYNC)") (class "Default")
      (node (ref "IC3") (pin "15") (pinfunction "RT/SYNC_15") (pintype "input"))
      (node (ref "R46") (pin "1") (pinfunction "1_1") (pintype "passive"))
    )
    (net (code "73") (name "Net-(IC3-SS)") (class "Default")
      (node (ref "C43") (pin "2") (pinfunction "2_2") (pintype "passive"))
      (node (ref "IC3") (pin "13") (pinfunction "SS_13") (pintype "passive"))
    )
    (net (code "74") (name "Net-(IC3-TIME)") (class "Default")
      (node (ref "IC3") (pin "14") (pinfunction "TIME_14") (pintype "input"))
      (node (ref "R45") (pin "1") (pinfunction "1_1") (pintype "passive"))
    )
    (net (code "75") (name "Net-(IC3-UVLO)") (class "Default")
      (node (ref "C40") (pin "1") (pinfunction "1_1") (pintype "passive"))
      (node (ref "IC3") (pin "16") (pinfunction "UVLO_16") (pintype "input"))
      (node (ref "R39") (pin "1") (pinfunction "1_1") (pintype "passive"))
      (node (ref "ZD4") (pin "C") (pinfunction "C_C") (pintype "passive"))
    )
    (net (code "76") (name "Net-(IC3-VCC)") (class "Default")
      (node (ref "C41") (pin "1") (pinfunction "1_1") (pintype "passive"))
      (node (ref "C42") (pin "1") (pinfunction "1_1") (pintype "passive"))
      (node (ref "IC3") (pin "1") (pinfunction "VIN_1") (pintype "input"))
      (node (ref "IC3") (pin "7") (pinfunction "VCC_7") (pintype "power_in"))
      (node (ref "R40") (pin "1") (pinfunction "1_1") (pintype "passive"))
    )
    (net (code "77") (name "Net-(IC4A-+IN)") (class "Default")
      (node (ref "C53") (pin "2") (pinfunction "2_2") (pintype "passive"))
      (node (ref "IC4") (pin "3") (pinfunction "+IN_3") (pintype "input"))
      (node (ref "R57") (pin "2") (pinfunction "2_2") (pintype "passive"))
    )
    (net (code "78") (name "Net-(IC4A--IN)") (class "Default")
      (node (ref "C51") (pin "1") (pinfunction "1_1") (pintype "passive"))
      (node (ref "D23") (pin "C") (pinfunction "C_C") (pintype "passive"))
      (node (ref "IC4") (pin "2") (pinfunction "-IN_2") (pintype "input"))
      (node (ref "R56") (pin "1") (pinfunction "1_1") (pintype "passive"))
      (node (ref "R61") (pin "1") (pinfunction "1_1") (pintype "passive"))
    )
    (net (code "79") (name "Net-(IC4A-OUT)") (class "Default")
      (node (ref "D22") (pin "A") (pinfunction "A_A") (pintype "passive"))
      (node (ref "IC4") (pin "1") (pinfunction "OUT_1") (pintype "output"))
    )
    (net (code "80") (name "Net-(IC4B-+IN)") (class "Default")
      (node (ref "C52") (pin "2") (pinfunction "2_2") (pintype "passive"))
      (node (ref "IC4") (pin "5") (pinfunction "+IN_5") (pintype "input"))
      (node (ref "R60") (pin "1") (pinfunction "1_1") (pintype "passive"))
      (node (ref "X3") (pin "1") (pinfunction "1_1") (pintype "passive"))
    )
    (net (code "81") (name "Net-(IC4B--IN)") (class "Default")
      (node (ref "IC4") (pin "6") (pinfunction "-IN_6") (pintype "input"))
      (node (ref "R55") (pin "1") (pinfunction "1_1") (pintype "passive"))
      (node (ref "R59") (pin "1") (pinfunction "1_1") (pintype "passive"))
    )
    (net (code "82") (name "Net-(IC4B-OUT)") (class "Default")
      (node (ref "D24") (pin "A") (pinfunction "A_A") (pintype "passive"))
      (node (ref "IC4") (pin "7") (pinfunction "OUT_7") (pintype "output"))
    )
    (net (code "83") (name "Net-(IC5-GATE1)") (class "Default")
      (node (ref "D25") (pin "C") (pinfunction "C_C") (pintype "passive"))
      (node (ref "IC5") (pin "1") (pinfunction "GATE1_1") (pintype "output"))
      (node (ref "R68") (pin "2") (pinfunction "2_2") (pintype "passive"))
    )
    (net (code "84") (name "Net-(IC5-GATE2)") (class "Default")
      (node (ref "D26") (pin "C") (pinfunction "C_C") (pintype "passive"))
      (node (ref "IC5") (pin "8") (pinfunction "GATE2_8") (pintype "output"))
      (node (ref "R71") (pin "2") (pinfunction "2_2") (pintype "passive"))
    )
    (net (code "85") (name "Net-(IC5-MOT)") (class "Default")
      (node (ref "IC5") (pin "3") (pinfunction "MOT_3") (pintype "passive"))
      (node (ref "R70") (pin "1") (pinfunction "1_1") (pintype "passive"))
    )
    (net (code "86") (name "Net-(IC5-VCC)") (class "Default")
      (node (ref "C64") (pin "1") (pinfunction "1_1") (pintype "passive"))
      (node (ref "C65") (pin "1") (pinfunction "1_1") (pintype "passive"))
      (node (ref "IC5") (pin "2") (pinfunction "VCC_2") (pintype "power_in"))
      (node (ref "R69") (pin "2") (pinfunction "2_2") (pintype "passive"))
    )
    (net (code "87") (name "Net-(IC6A--IN)") (class "Default")
      (node (ref "C75") (pin "2") (pinfunction "2_2") (pintype "passive"))
      (node (ref "IC6") (pin "2") (pinfunction "-IN_2") (pintype "input"))
      (node (ref "R79") (pin "1") (pinfunction "1_1") (pintype "passive"))
      (node (ref "R82") (pin "2") (pinfunction "2_2") (pintype "passive"))
      (node (ref "R86") (pin "1") (pinfunction "1_1") (pintype "passive"))
    )
    (net (code "88") (name "Net-(IC6A-OUT)") (class "Default")
      (node (ref "C75") (pin "1") (pinfunction "1_1") (pintype "passive"))
      (node (ref "IC6") (pin "1") (pinfunction "OUT_1") (pintype "output"))
      (node (ref "R89") (pin "2") (pinfunction "2_2") (pintype "passive"))
    )
    (net (code "89") (name "Net-(IC6B--IN)") (class "Default")
      (node (ref "IC6") (pin "6") (pinfunction "-IN_6") (pintype "input"))
      (node (ref "R74") (pin "2") (pinfunction "2_2") (pintype "passive"))
      (node (ref "R78") (pin "1") (pinfunction "1_1") (pintype "passive"))
    )
    (net (code "90") (name "Net-(IC6B-OUT)") (class "Default")
      (node (ref "IC6") (pin "7") (pinfunction "OUT_7") (pintype "output"))
      (node (ref "R74") (pin "1") (pinfunction "1_1") (pintype "passive"))
      (node (ref "R79") (pin "2") (pinfunction "2_2") (pintype "passive"))
    )
    (net (code "91") (name "Net-(IC6C-V+)") (class "Default")
      (node (ref "C70") (pin "1") (pinfunction "1_1") (pintype "passive"))
      (node (ref "C72") (pin "1") (pinfunction "1_1") (pintype "passive"))
      (node (ref "IC6") (pin "8") (pinfunction "V+_8") (pintype "power_in"))
      (node (ref "IC7") (pin "8") (pinfunction "VCC+_8") (pintype "power_in"))
      (node (ref "JP6") (pin "2") (pinfunction "2_2") (pintype "passive"))
      (node (ref "R69") (pin "1") (pinfunction "1_1") (pintype "passive"))
      (node (ref "R84") (pin "2") (pinfunction "2_2") (pintype "passive"))
      (node (ref "R85") (pin "2") (pinfunction "2_2") (pintype "passive"))
    )
    (net (code "92") (name "Net-(IC6C-V-)") (class "Default")
      (node (ref "C74") (pin "1") (pinfunction "1_1") (pintype "passive"))
      (node (ref "IC6") (pin "4") (pinfunction "V-_4") (pintype "power_in"))
      (node (ref "JP7") (pin "1") (pinfunction "1_1") (pintype "passive"))
    )
    (net (code "93") (name "Net-(IC7A--IN1)") (class "Default")
      (node (ref "C73") (pin "2") (pinfunction "2_2") (pintype "passive"))
      (node (ref "IC7") (pin "2") (pinfunction "-IN1_2") (pintype "input"))
      (node (ref "R83") (pin "1") (pinfunction "1_1") (pintype "passive"))
      (node (ref "R87") (pin "1") (pinfunction "1_1") (pintype "passive"))
    )
    (net (code "94") (name "Net-(IC7A-OUT1)") (class "Default")
      (node (ref "C73") (pin "1") (pinfunction "1_1") (pintype "passive"))
      (node (ref "C76") (pin "1") (pinfunction "1_1") (pintype "passive"))
      (node (ref "IC7") (pin "1") (pinfunction "OUT1_1") (pintype "output"))
      (node (ref "OK3") (pin "2") (pinfunction "C_2") (pintype "passive"))
    )
    (net (code "95") (name "Net-(IC7B-+IN)") (class "Default")
      (node (ref "C79") (pin "1") (pinfunction "1_1") (pintype "passive"))
      (node (ref "IC7") (pin "5") (pinfunction "+IN_5") (pintype "input"))
      (node (ref "JP8") (pin "COM") (pinfunction "COM_COM") (pintype "passive"))
    )
    (net (code "96") (name "Net-(IC7B--IN)") (class "Default")
      (node (ref "IC7") (pin "6") (pinfunction "-IN_6") (pintype "input"))
      (node (ref "IC7") (pin "7") (pinfunction "OUT_7") (pintype "output"))
      (node (ref "R86") (pin "2") (pinfunction "2_2") (pintype "passive"))
    )
    (net (code "97") (name "Net-(JP8-PadNO)") (class "Default")
      (node (ref "JP8") (pin "NO") (pinfunction "NO_NO") (pintype "passive"))
      (node (ref "P1") (pin "S") (pinfunction "S_S") (pintype "passive"))
    )
    (net (code "98") (name "Net-(L1B-1)") (class "Default")
      (node (ref "B1") (pin "AC1") (pinfunction "AC1_AC1") (pintype "passive"))
      (node (ref "C2") (pin "1") (pinfunction "1_1") (pintype "passive"))
      (node (ref "C5") (pin "2") (pinfunction "2_2") (pintype "passive"))
      (node (ref "L1") (pin "3") (pinfunction "1_3") (pintype "passive"))
      (node (ref "SAR1") (pin "2") (pinfunction "P$2_2") (pintype "bidirectional"))
    )
    (net (code "99") (name "Net-(L3-2)") (class "Default")
      (node (ref "C12") (pin "1") (pinfunction "1_1") (pintype "passive"))
      (node (ref "C13") (pin "+") (pinfunction "+_+") (pintype "passive"))
      (node (ref "JP2") (pin "2") (pinfunction "2_2") (pintype "passive"))
      (node (ref "L3") (pin "P$2") (pinfunction "2_P$2") (pintype "passive"))
      (node (ref "R6") (pin "1") (pinfunction "1_1") (pintype "passive"))
      (node (ref "R7") (pin "1") (pinfunction "1_1") (pintype "passive"))
      (node (ref "TR1") (pin "1") (pinfunction "SHIELD_1") (pintype "passive"))
      (node (ref "TR1") (pin "2") (pinfunction "P_2") (pintype "passive"))
    )
    (net (code "100") (name "Net-(LED1A-A)") (class "Default")
      (node (ref "LED1") (pin "BA") (pinfunction "A_BA") (pintype "passive"))
      (node (ref "R75") (pin "2") (pinfunction "2_2") (pintype "passive"))
    )
    (net (code "101") (name "Net-(LED1B-A)") (class "Default")
      (node (ref "LED1") (pin "TA") (pinfunction "A_TA") (pintype "passive"))
      (node (ref "R76") (pin "2") (pinfunction "2_2") (pintype "passive"))
    )
    (net (code "102") (name "Net-(OK1-A)") (class "Default")
      (node (ref "OK1") (pin "1") (pinfunction "A_1") (pintype "passive"))
      (node (ref "R13") (pin "2") (pinfunction "2_2") (pintype "passive"))
    )
    (net (code "103") (name "Net-(OK1-C)") (class "Default")
      (node (ref "OK1") (pin "2") (pinfunction "C_2") (pintype "passive"))
      (node (ref "R17") (pin "1") (pinfunction "1_1") (pintype "passive"))
      (node (ref "ZD3") (pin "C") (pinfunction "C_C") (pintype "passive"))
    )
    (net (code "104") (name "Net-(OK2-C)") (class "Default")
      (node (ref "OK2") (pin "2") (pinfunction "C_2") (pintype "passive"))
      (node (ref "R35") (pin "1") (pinfunction "1_1") (pintype "passive"))
    )
    (net (code "105") (name "Net-(OK3-A)") (class "Default")
      (node (ref "OK3") (pin "1") (pinfunction "A_1") (pintype "passive"))
      (node (ref "R85") (pin "1") (pinfunction "1_1") (pintype "passive"))
    )
    (net (code "106") (name "Net-(OK3-COL)") (class "Default")
      (node (ref "JP9") (pin "2") (pinfunction "2_2") (pintype "passive"))
      (node (ref "OK3") (pin "4") (pinfunction "COL_4") (pintype "passive"))
    )
    (net (code "107") (name "Net-(Q4-A)") (class "Default")
      (node (ref "D16") (pin "C") (pinfunction "C_C") (pintype "passive"))
      (node (ref "D17") (pin "C") (pinfunction "C_C") (pintype "passive"))
      (node (ref "Q4") (pin "3") (pinfunction "A_3") (pintype "passive"))
    )
    (net (code "108") (name "Net-(Q4-G)") (class "Default")
      (node (ref "C44") (pin "1") (pinfunction "1_1") (pintype "passive"))
      (node (ref "Q4") (pin "2") (pinfunction "G_2") (pintype "passive"))
      (node (ref "R51") (pin "1") (pinfunction "1_1") (pintype "passive"))
    )
    (net (code "109") (name "Net-(R1-Pad2)") (class "Default")
      (node (ref "R1") (pin "2") (pinfunction "2_2") (pintype "passive"))
      (node (ref "R2") (pin "1") (pinfunction "1_1") (pintype "passive"))
    )
    (net (code "110") (name "Net-(R7-Pad2)") (class "Default")
      (node (ref "R7") (pin "2") (pinfunction "2_2") (pintype "passive"))
      (node (ref "R8") (pin "1") (pinfunction "1_1") (pintype "passive"))
    )
    (net (code "111") (name "Net-(R24-Pad1)") (class "Default")
      (node (ref "R24") (pin "1") (pinfunction "1_1") (pintype "passive"))
      (node (ref "R25") (pin "2") (pinfunction "2_2") (pintype "passive"))
    )
    (net (code "112") (name "Net-(R29-Pad2)") (class "Default")
      (node (ref "R29") (pin "2") (pinfunction "2_2") (pintype "passive"))
      (node (ref "R36") (pin "1") (pinfunction "1_1") (pintype "passive"))
      (node (ref "TP2") (pin "1") (pinfunction "1_1") (pintype "passive"))
    )
    (net (code "113") (name "Net-(R42-Pad2)") (class "Default")
      (node (ref "R42") (pin "2") (pinfunction "2_2") (pintype "passive"))
      (node (ref "R43") (pin "1") (pinfunction "1_1") (pintype "passive"))
    )
    (net (code "114") (name "Net-(R77-Pad1)") (class "Default")
      (node (ref "R77") (pin "1") (pinfunction "1_1") (pintype "passive"))
      (node (ref "R81") (pin "2") (pinfunction "2_2") (pintype "passive"))
    )
    (net (code "115") (name "Net-(R80-Pad1)") (class "Default")
      (node (ref "R80") (pin "1") (pinfunction "1_1") (pintype "passive"))
      (node (ref "R81") (pin "1") (pinfunction "1_1") (pintype "passive"))
      (node (ref "R87") (pin "2") (pinfunction "2_2") (pintype "passive"))
      (node (ref "R88") (pin "2") (pinfunction "2_2") (pintype "passive"))
    )
    (net (code "116") (name "Net-(SAR2-P$2)") (class "Default")
      (node (ref "B1") (pin "AC2") (pinfunction "AC2_AC2") (pintype "passive"))
      (node (ref "C2") (pin "2") (pinfunction "2_2") (pintype "passive"))
      (node (ref "C4") (pin "2") (pinfunction "2_2") (pintype "passive"))
      (node (ref "L1") (pin "1") (pinfunction "1_1") (pintype "passive"))
      (node (ref "SAR2") (pin "2") (pinfunction "P$2_2") (pintype "bidirectional"))
    )
    (net (code "117") (name "Net-(TR1-P2_DOT)") (class "Default")
      (node (ref "D3") (pin "A") (pinfunction "A_A") (pintype "passive"))
      (node (ref "IC1") (pin "13") (pinfunction "DRAIN_13") (pintype "output"))
      (node (ref "IC1") (pin "14") (pinfunction "DRAIN_14") (pintype "output"))
      (node (ref "IC1") (pin "15") (pinfunction "DRAIN_15") (pintype "output"))
      (node (ref "IC1") (pin "16") (pinfunction "DRAIN_16") (pintype "output"))
      (node (ref "TR1") (pin "4") (pinfunction "P2_DOT_4") (pintype "passive"))
    )
    (net (code "118") (name "Net-(TR1-S2)") (class "Default")
      (node (ref "C16") (pin "2") (pinfunction "2_2") (pintype "passive"))
      (node (ref "D4") (pin "C") (pinfunction "C_C") (pintype "passive"))
      (node (ref "TR1") (pin "8") (pinfunction "S2_8") (pintype "passive"))
    )
    (net (code "119") (name "Net-(TR1-S3_DOT)") (class "Default")
      (node (ref "C9") (pin "2") (pinfunction "2_2") (pintype "passive"))
      (node (ref "D2") (pin "A") (pinfunction "A_A") (pintype "passive"))
      (node (ref "TR1") (pin "15") (pinfunction "S3_DOT_15") (pintype "passive"))
    )
    (net (code "120") (name "Net-(TR2-P_DOT)") (class "Default")
      (node (ref "Q2") (pin "D") (pinfunction "D_D") (pintype "passive"))
      (node (ref "TR2") (pin "8") (pinfunction "P_DOT_8") (pintype "passive"))
    )
    (net (code "121") (name "Net-(X2D-1)") (class "Default")
      (node (ref "D27") (pin "A") (pinfunction "A_A") (pintype "passive"))
      (node (ref "X2") (pin "4") (pinfunction "1_4") (pintype "passive"))
    )
    (net (code "122") (name "Net-(X2E-1)") (class "Default")
      (node (ref "JP8") (pin "NC") (pinfunction "NC_NC") (pintype "passive"))
      (node (ref "X2") (pin "5") (pinfunction "1_5") (pintype "passive"))
    )
    (net (code "123") (name "PE") (class "Default")
      (node (ref "C4") (pin "1") (pinfunction "1_1") (pintype "passive"))
      (node (ref "C4A") (pin "1") (pinfunction "1_1") (pintype "passive"))
      (node (ref "C5") (pin "1") (pinfunction "1_1") (pintype "passive"))
      (node (ref "C5A") (pin "1") (pinfunction "1_1") (pintype "passive"))
      (node (ref "C66") (pin "2") (pinfunction "2_2") (pintype "passive"))
      (node (ref "C67") (pin "2") (pinfunction "2_2") (pintype "passive"))
      (node (ref "C68") (pin "2") (pinfunction "2_2") (pintype "passive"))
      (node (ref "JP4") (pin "NC") (pinfunction "NC_NC") (pintype "passive"))
      (node (ref "X1") (pin "3") (pinfunction "1_3") (pintype "passive"))
    )
    (net (code "124") (name "POUT+") (class "Default")
      (node (ref "C54") (pin "+") (pinfunction "+_+") (pintype "passive"))
      (node (ref "C55") (pin "+") (pinfunction "+_+") (pintype "passive"))
      (node (ref "C56") (pin "+") (pinfunction "+_+") (pintype "passive"))
      (node (ref "C57") (pin "1") (pinfunction "1_1") (pintype "passive"))
      (node (ref "C66") (pin "1") (pinfunction "1_1") (pintype "passive"))
      (node (ref "L8") (pin "1") (pinfunction "1_1") (pintype "passive"))
      (node (ref "R63") (pin "1") (pinfunction "1_1") (pintype "passive"))
      (node (ref "SH2") (pin "P$2") (pinfunction "GND_B_P$2") (pintype "bidirectional"))
      (node (ref "SH3") (pin "P$1") (pinfunction "GND_A_P$1") (pintype "bidirectional"))
    )
    (net (code "125") (name "PREG_OUT+") (class "Default")
      (node (ref "C58") (pin "+") (pinfunction "+_+") (pintype "passive"))
      (node (ref "C59") (pin "+") (pinfunction "+_+") (pintype "passive"))
      (node (ref "C60") (pin "1") (pinfunction "1_1") (pintype "passive"))
      (node (ref "C61") (pin "1") (pinfunction "1_1") (pintype "passive"))
      (node (ref "C67") (pin "1") (pinfunction "1_1") (pintype "passive"))
      (node (ref "C71") (pin "1") (pinfunction "1_1") (pintype "passive"))
      (node (ref "JP3") (pin "NC") (pinfunction "NC_NC") (pintype "passive"))
      (node (ref "L8") (pin "2") (pinfunction "2_2") (pintype "passive"))
      (node (ref "R63") (pin "2") (pinfunction "2_2") (pintype "passive"))
      (node (ref "R64") (pin "2") (pinfunction "2_2") (pintype "passive"))
      (node (ref "R67") (pin "2") (pinfunction "2_2") (pintype "passive"))
      (node (ref "R77") (pin "2") (pinfunction "2_2") (pintype "passive"))
      (node (ref "TP6") (pin "TIP") (pinfunction "TIP_TIP") (pintype "bidirectional"))
      (node (ref "X4") (pin "1") (pinfunction "1_1") (pintype "passive"))
      (node (ref "ZD5") (pin "C") (pinfunction "C_C") (pintype "passive"))
    )
    (net (code "126") (name "PULL") (class "Default")
      (node (ref "D21") (pin "A") (pinfunction "A_A") (pintype "passive"))
      (node (ref "IC3") (pin "9") (pinfunction "PULL_9") (pintype "output"))
      (node (ref "R47") (pin "2") (pinfunction "2_2") (pintype "passive"))
    )
    (net (code "127") (name "PUSH") (class "Default")
      (node (ref "D19") (pin "A") (pinfunction "A_A") (pintype "passive"))
      (node (ref "IC3") (pin "8") (pinfunction "PUSH_8") (pintype "output"))
      (node (ref "R44") (pin "2") (pinfunction "2_2") (pintype "passive"))
    )
    (net (code "128") (name "REF") (class "Default")
      (node (ref "C34") (pin "2") (pinfunction "2_2") (pintype "passive"))
      (node (ref "IC2") (pin "3") (pinfunction "VDDI_3") (pintype "power_in"))
      (node (ref "IC2") (pin "8") (pinfunction "VDDI_8") (pintype "power_in"))
      (node (ref "R38") (pin "2") (pinfunction "2_2") (pintype "passive"))
    )
    (net (code "129") (name "S1_DOT_OUT") (class "Default")
      (node (ref "IC5") (pin "4") (pinfunction "VD1_4") (pintype "passive"))
      (node (ref "Q7") (pin "3") (pinfunction "D_3") (pintype "passive"))
      (node (ref "R65") (pin "1") (pinfunction "1_1") (pintype "passive"))
      (node (ref "R66") (pin "1") (pinfunction "1_1") (pintype "passive"))
      (node (ref "TR3") (pin "S1_DOT") (pinfunction "S1_DOT_S1_DOT") (pintype "passive"))
    )
    (net (code "130") (name "S1_OUT") (class "Default")
      (node (ref "SH2") (pin "P$1") (pinfunction "GND_A_P$1") (pintype "bidirectional"))
      (node (ref "TR3") (pin "S1") (pinfunction "S1_S1") (pintype "passive"))
    )
    (net (code "131") (name "S2_DOT_OUT") (class "Default")
      (node (ref "SH3") (pin "P$2") (pinfunction "GND_B_P$2") (pintype "bidirectional"))
      (node (ref "TR3") (pin "S2_DOT") (pinfunction "S2_DOT_S2_DOT") (pintype "passive"))
    )
    (net (code "132") (name "S2_OUT") (class "Default")
      (node (ref "IC5") (pin "5") (pinfunction "VD2_5") (pintype "passive"))
      (node (ref "Q8") (pin "3") (pinfunction "D_3") (pintype "passive"))
      (node (ref "R72") (pin "1") (pinfunction "1_1") (pintype "passive"))
      (node (ref "R73") (pin "1") (pinfunction "1_1") (pintype "passive"))
      (node (ref "TR3") (pin "S2") (pinfunction "S2_S2") (pintype "passive"))
    )
    (net (code "133") (name "SR_OUT1") (class "Default")
      (node (ref "D25") (pin "A") (pinfunction "A_A") (pintype "passive"))
      (node (ref "Q7") (pin "1") (pinfunction "G_1") (pintype "passive"))
      (node (ref "R68") (pin "1") (pinfunction "1_1") (pintype "passive"))
    )
    (net (code "134") (name "SR_OUT2") (class "Default")
      (node (ref "D26") (pin "A") (pinfunction "A_A") (pintype "passive"))
      (node (ref "Q8") (pin "1") (pinfunction "G_1") (pintype "passive"))
      (node (ref "R71") (pin "1") (pinfunction "1_1") (pintype "passive"))
    )
    (net (code "135") (name "V+") (class "Default")
      (node (ref "C22") (pin "1") (pinfunction "1_1") (pintype "passive"))
      (node (ref "JP6") (pin "1") (pinfunction "1_1") (pintype "passive"))
      (node (ref "L5") (pin "2") (pinfunction "2_2") (pintype "passive"))
      (node (ref "R17") (pin "2") (pinfunction "2_2") (pintype "passive"))
      (node (ref "R75") (pin "1") (pinfunction "1_1") (pintype "passive"))
      (node (ref "R76") (pin "1") (pinfunction "1_1") (pintype "passive"))
      (node (ref "X2") (pin "3") (pinfunction "1_3") (pintype "passive"))
    )
    (net (code "136") (name "V-") (class "Default")
      (node (ref "C15") (pin "2") (pinfunction "2_2") (pintype "passive"))
      (node (ref "JP7") (pin "2") (pinfunction "2_2") (pintype "passive"))
      (node (ref "L4") (pin "2") (pinfunction "2_2") (pintype "passive"))
      (node (ref "X2") (pin "1") (pinfunction "1_1") (pintype "passive"))
    )
    (net (code "137") (name "~{FAULT}") (class "Default")
      (node (ref "D27") (pin "C") (pinfunction "C_C") (pintype "passive"))
      (node (ref "LED1") (pin "BC") (pinfunction "C_BC") (pintype "passive"))
      (node (ref "OK2") (pin "4") (pinfunction "COL_4") (pintype "passive"))
    )
  )
)
